# keyboard_main.net
KiCad netlist of a schematic drawn in Altium Designer
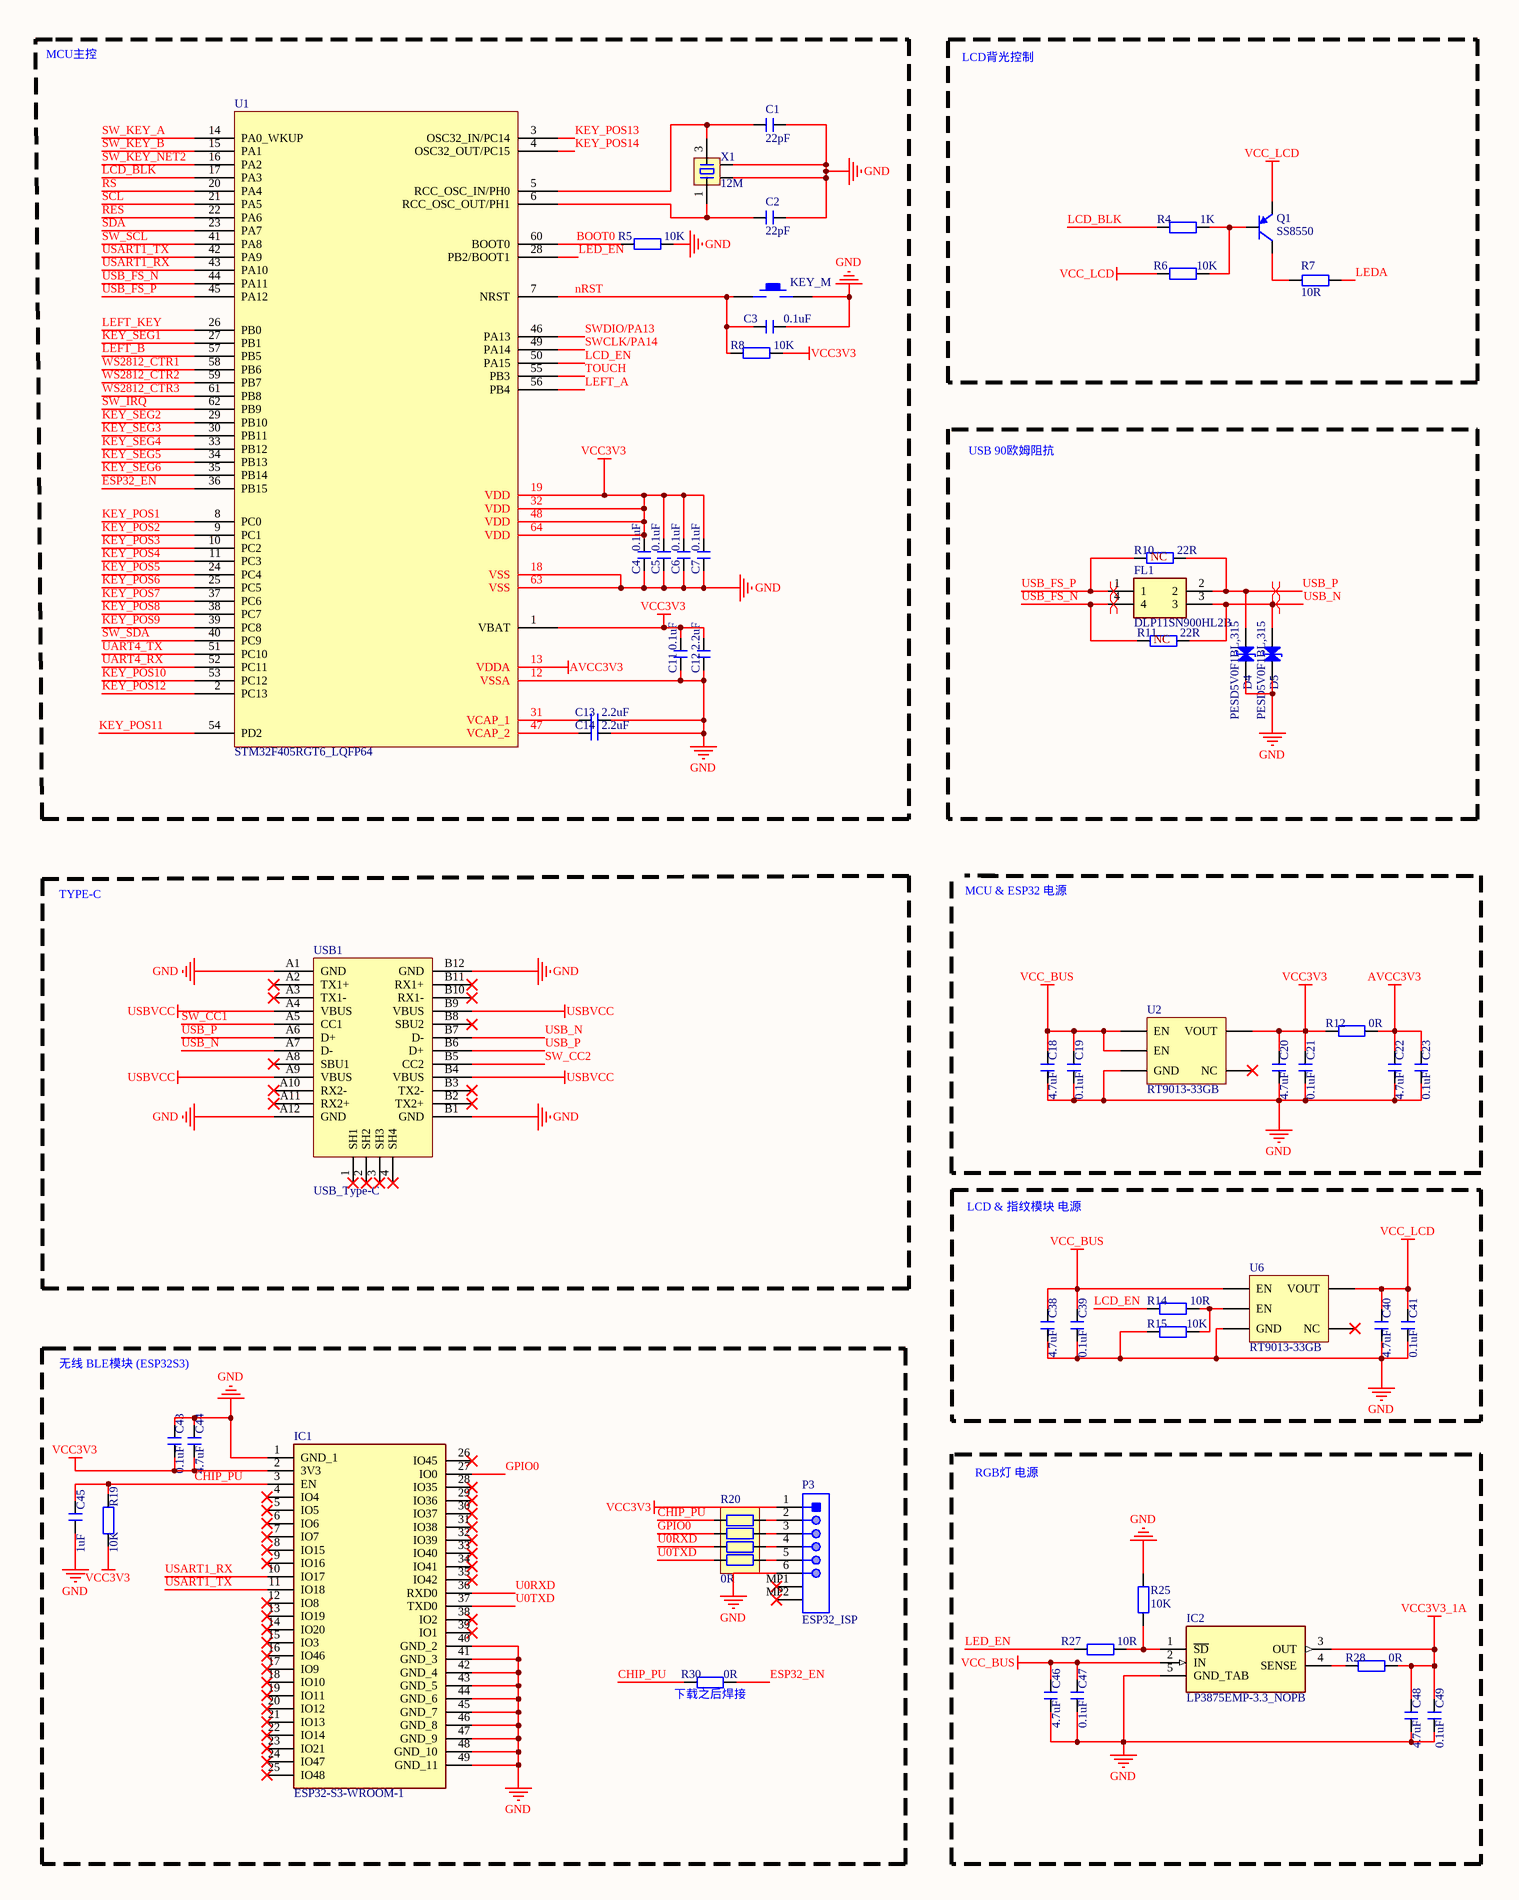
[diagram p0: keyboard_main.SchDoc, left]
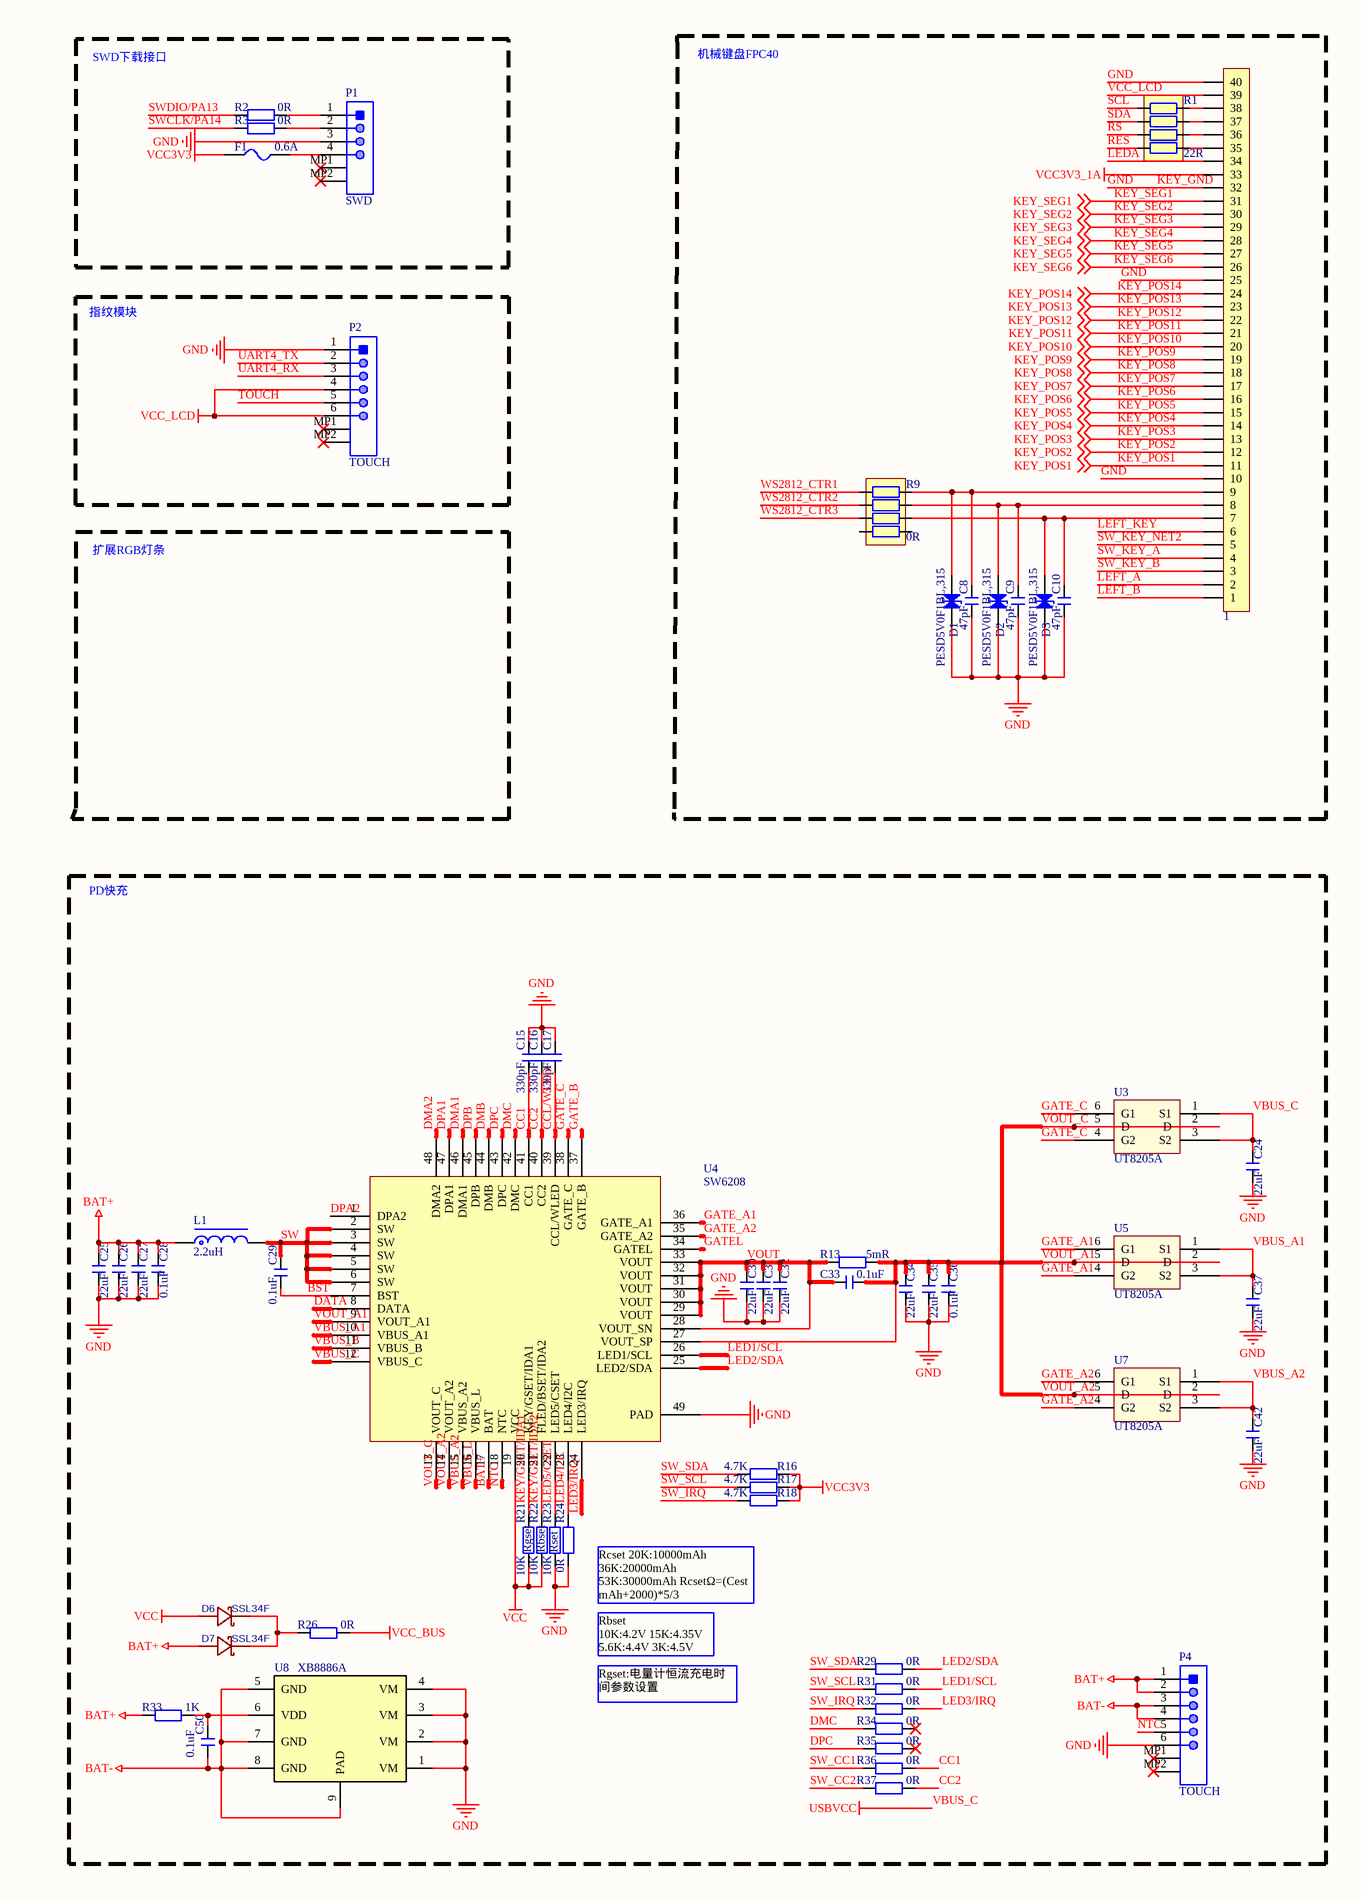
[diagram p1: keyboard_main.SchDoc, right]

(export (version "E")
  (design (tool "Eeschema 10.0.6"))
  (components
    (comp (ref "1")
      (value "FPC1.0-40P")
      (footprint "FPC0.5 2H-WS-40P")
      (description "FPC连接器")
      (fields (field (name "版权归属") "黎明电子style"))
      (libsource (lib "FPC连接器") (part "FPC-40P"))
    )
    (comp (ref "C1")
      (value "22pF")
      (footprint "C 0402_L")
      (description "贴片电容")
      (libsource (lib "0.1 - 电阻-电容-电感") (part "C"))
    )
    (comp (ref "C2")
      (value "22pF")
      (footprint "C 0402_L")
      (description "贴片电容")
      (libsource (lib "0.1 - 电阻-电容-电感") (part "C"))
    )
    (comp (ref "C3")
      (value "0.1uF")
      (footprint "C 0402_L")
      (description "贴片电容")
      (libsource (lib "0.1 - 电阻-电容-电感") (part "C"))
    )
    (comp (ref "C4")
      (value "0.1uF")
      (footprint "C 0402_L")
      (description "贴片电容")
      (libsource (lib "0.1 - 电阻-电容-电感") (part "C"))
    )
    (comp (ref "C5")
      (value "0.1uF")
      (footprint "C 0402_L")
      (description "贴片电容")
      (libsource (lib "0.1 - 电阻-电容-电感") (part "C"))
    )
    (comp (ref "C6")
      (value "0.1uF")
      (footprint "C 0402_L")
      (description "贴片电容")
      (libsource (lib "0.1 - 电阻-电容-电感") (part "C"))
    )
    (comp (ref "C7")
      (value "0.1uF")
      (footprint "C 0402_L")
      (description "贴片电容")
      (libsource (lib "0.1 - 电阻-电容-电感") (part "C"))
    )
    (comp (ref "C8")
      (value "47pF")
      (footprint "C 0402_L")
      (description "贴片电容")
      (libsource (lib "0.1 - 电阻-电容-电感") (part "C"))
    )
    (comp (ref "C9")
      (value "47pF")
      (footprint "C 0402_L")
      (description "贴片电容")
      (libsource (lib "0.1 - 电阻-电容-电感") (part "C"))
    )
    (comp (ref "C10")
      (value "47pF")
      (footprint "C 0402_L")
      (description "贴片电容")
      (libsource (lib "0.1 - 电阻-电容-电感") (part "C"))
    )
    (comp (ref "C11")
      (value "0.1uF")
      (footprint "C 0402_L")
      (description "贴片电容")
      (libsource (lib "0.1 - 电阻-电容-电感") (part "C"))
    )
    (comp (ref "C12")
      (value "2.2uF")
      (footprint "C 0402_L")
      (description "贴片电容")
      (libsource (lib "0.1 - 电阻-电容-电感") (part "C"))
    )
    (comp (ref "C13")
      (value "2.2uF")
      (footprint "C 0402_L")
      (description "贴片电容")
      (libsource (lib "0.1 - 电阻-电容-电感") (part "C"))
    )
    (comp (ref "C14")
      (value "2.2uF")
      (footprint "C 0402_L")
      (description "贴片电容")
      (libsource (lib "0.1 - 电阻-电容-电感") (part "C"))
    )
    (comp (ref "C15")
      (value "330pF")
      (footprint "C 0402_L")
      (description "贴片电容")
      (libsource (lib "0.1 - 电阻-电容-电感") (part "C"))
    )
    (comp (ref "C16")
      (value "330pF")
      (footprint "C 0402_L")
      (description "贴片电容")
      (libsource (lib "0.1 - 电阻-电容-电感") (part "C"))
    )
    (comp (ref "C17")
      (value "330pF")
      (footprint "C 0402_L")
      (description "贴片电容")
      (libsource (lib "0.1 - 电阻-电容-电感") (part "C"))
    )
    (comp (ref "C18")
      (value "4.7uF")
      (footprint "C 0402_L")
      (description "贴片电容")
      (libsource (lib "0.1 - 电阻-电容-电感") (part "C"))
    )
    (comp (ref "C19")
      (value "0.1uF")
      (footprint "C 0402_L")
      (description "贴片电容")
      (libsource (lib "0.1 - 电阻-电容-电感") (part "C"))
    )
    (comp (ref "C20")
      (value "4.7uF")
      (footprint "C 0402_L")
      (description "贴片电容")
      (libsource (lib "0.1 - 电阻-电容-电感") (part "C"))
    )
    (comp (ref "C21")
      (value "0.1uF")
      (footprint "C 0402_L")
      (description "贴片电容")
      (libsource (lib "0.1 - 电阻-电容-电感") (part "C"))
    )
    (comp (ref "C22")
      (value "4.7uF")
      (footprint "C 0402_L")
      (description "贴片电容")
      (libsource (lib "0.1 - 电阻-电容-电感") (part "C"))
    )
    (comp (ref "C23")
      (value "0.1uF")
      (footprint "C 0402_L")
      (description "贴片电容")
      (libsource (lib "0.1 - 电阻-电容-电感") (part "C"))
    )
    (comp (ref "C24")
      (value "22uF")
      (footprint "C 0805_L")
      (description "贴片电容")
      (libsource (lib "0.1 - 电阻-电容-电感") (part "C"))
    )
    (comp (ref "C25")
      (value "22uF")
      (footprint "C 0805_L")
      (description "贴片电容")
      (libsource (lib "0.1 - 电阻-电容-电感") (part "C"))
    )
    (comp (ref "C26")
      (value "22uF")
      (footprint "C 0805_L")
      (description "贴片电容")
      (libsource (lib "0.1 - 电阻-电容-电感") (part "C"))
    )
    (comp (ref "C27")
      (value "22uF")
      (footprint "C 0805_L")
      (description "贴片电容")
      (libsource (lib "0.1 - 电阻-电容-电感") (part "C"))
    )
    (comp (ref "C28")
      (value "0.1uF")
      (footprint "C 0805_L")
      (description "贴片电容")
      (libsource (lib "0.1 - 电阻-电容-电感") (part "C"))
    )
    (comp (ref "C29")
      (value "0.1uF")
      (footprint "C 0603_L")
      (description "贴片电容")
      (libsource (lib "0.1 - 电阻-电容-电感") (part "C"))
    )
    (comp (ref "C30")
      (value "22uF")
      (footprint "C 0805_L")
      (description "贴片电容")
      (libsource (lib "0.1 - 电阻-电容-电感") (part "C"))
    )
    (comp (ref "C31")
      (value "22uF")
      (footprint "C 0805_L")
      (description "贴片电容")
      (libsource (lib "0.1 - 电阻-电容-电感") (part "C"))
    )
    (comp (ref "C32")
      (value "22uF")
      (footprint "C 0805_L")
      (description "贴片电容")
      (libsource (lib "0.1 - 电阻-电容-电感") (part "C"))
    )
    (comp (ref "C33")
      (value "0.1uF")
      (footprint "C 0805_L")
      (description "贴片电容")
      (libsource (lib "0.1 - 电阻-电容-电感") (part "C"))
    )
    (comp (ref "C34")
      (value "22uF")
      (footprint "C 0805_L")
      (description "贴片电容")
      (libsource (lib "0.1 - 电阻-电容-电感") (part "C"))
    )
    (comp (ref "C35")
      (value "22uF")
      (footprint "C 0805_L")
      (description "贴片电容")
      (libsource (lib "0.1 - 电阻-电容-电感") (part "C"))
    )
    (comp (ref "C36")
      (value "0.1uF")
      (footprint "C 0805_L")
      (description "贴片电容")
      (libsource (lib "0.1 - 电阻-电容-电感") (part "C"))
    )
    (comp (ref "C37")
      (value "22uF")
      (footprint "C 0805_L")
      (description "贴片电容")
      (libsource (lib "0.1 - 电阻-电容-电感") (part "C"))
    )
    (comp (ref "C38")
      (value "4.7uF")
      (footprint "C 0402_L")
      (description "贴片电容")
      (libsource (lib "0.1 - 电阻-电容-电感") (part "C"))
    )
    (comp (ref "C39")
      (value "0.1uF")
      (footprint "C 0402_L")
      (description "贴片电容")
      (libsource (lib "0.1 - 电阻-电容-电感") (part "C"))
    )
    (comp (ref "C40")
      (value "4.7uF")
      (footprint "C 0402_L")
      (description "贴片电容")
      (libsource (lib "0.1 - 电阻-电容-电感") (part "C"))
    )
    (comp (ref "C41")
      (value "0.1uF")
      (footprint "C 0402_L")
      (description "贴片电容")
      (libsource (lib "0.1 - 电阻-电容-电感") (part "C"))
    )
    (comp (ref "C42")
      (value "22uF")
      (footprint "C 0805_L")
      (description "贴片电容")
      (libsource (lib "0.1 - 电阻-电容-电感") (part "C"))
    )
    (comp (ref "C43")
      (value "0.1uF")
      (footprint "C 0402_L")
      (description "贴片电容")
      (libsource (lib "0.1 - 电阻-电容-电感") (part "C"))
    )
    (comp (ref "C44")
      (value "4.7uF")
      (footprint "C 0402_L")
      (description "贴片电容")
      (libsource (lib "0.1 - 电阻-电容-电感") (part "C"))
    )
    (comp (ref "C45")
      (value "1uF")
      (footprint "C 0402_L")
      (description "贴片电容")
      (libsource (lib "0.1 - 电阻-电容-电感") (part "C"))
    )
    (comp (ref "C46")
      (value "4.7uF")
      (footprint "C 0402_L")
      (description "贴片电容")
      (libsource (lib "0.1 - 电阻-电容-电感") (part "C"))
    )
    (comp (ref "C47")
      (value "0.1uF")
      (footprint "C 0402_L")
      (description "贴片电容")
      (libsource (lib "0.1 - 电阻-电容-电感") (part "C"))
    )
    (comp (ref "C48")
      (value "4.7uF")
      (footprint "C 0402_L")
      (description "贴片电容")
      (libsource (lib "0.1 - 电阻-电容-电感") (part "C"))
    )
    (comp (ref "C49")
      (value "0.1uF")
      (footprint "C 0402_L")
      (description "贴片电容")
      (libsource (lib "0.1 - 电阻-电容-电感") (part "C"))
    )
    (comp (ref "C50")
      (value "0.1uF")
      (footprint "C 0805_L")
      (description "贴片电容")
      (libsource (lib "0.1 - 电阻-电容-电感") (part "C"))
    )
    (comp (ref "D1")
      (value "PESD5V0F1BL,315")
      (footprint "SOD-882_L1.0-W0.6-BI")
      (description "PESD5V0F1BL,315、ESD二极管、5.5V")
      (libsource (lib "0.2 -  二极管-整流桥") (part "PESD5V0F1BL,315"))
    )
    (comp (ref "D2")
      (value "PESD5V0F1BL,315")
      (footprint "SOD-882_L1.0-W0.6-BI")
      (description "PESD5V0F1BL,315、ESD二极管、5.5V")
      (libsource (lib "0.2 -  二极管-整流桥") (part "PESD5V0F1BL,315"))
    )
    (comp (ref "D3")
      (value "PESD5V0F1BL,315")
      (footprint "SOD-882_L1.0-W0.6-BI")
      (description "PESD5V0F1BL,315、ESD二极管、5.5V")
      (libsource (lib "0.2 -  二极管-整流桥") (part "PESD5V0F1BL,315"))
    )
    (comp (ref "D4")
      (value "PESD5V0F1BL,315")
      (footprint "SOD-882_L1.0-W0.6-BI")
      (description "PESD5V0F1BL,315、ESD二极管、5.5V")
      (libsource (lib "0.2 -  二极管-整流桥") (part "PESD5V0F1BL,315"))
    )
    (comp (ref "D5")
      (value "PESD5V0F1BL,315")
      (footprint "SOD-882_L1.0-W0.6-BI")
      (description "PESD5V0F1BL,315、ESD二极管、5.5V")
      (libsource (lib "0.2 -  二极管-整流桥") (part "PESD5V0F1BL,315"))
    )
    (comp (ref "D6")
      (value "SSL34F")
      (footprint "SMAF_L3.5-W2.6-LS4.7-RD")
      (fields (field (name "BOM_SUPPLIER PART") "C1884559") (field (name "CONTRIBUTOR") "LCSC"))
      (libsource (lib "mx_pcb_library") (part "SSL34F_C1884559"))
    )
    (comp (ref "D7")
      (value "SSL34F")
      (footprint "SMAF_L3.5-W2.6-LS4.7-RD")
      (fields (field (name "BOM_SUPPLIER PART") "C1884559") (field (name "CONTRIBUTOR") "LCSC"))
      (libsource (lib "mx_pcb_library") (part "SSL34F_C1884559"))
    )
    (comp (ref "F1")
      (value "0.6A")
      (footprint "FU 0402")
      (description "贴片保险丝")
      (libsource (lib "2.0 - 保险丝-晶振-光耦") (part "FU"))
    )
    (comp (ref "FL1")
      (value "DLP11SN900HL2B")
      (footprint "vSeasky:DLP11SA350HL2B")
      (description "Filter")
      (fields (field (name "MOUSER PART NUMBER") "81-DLP11SN900HL2B"))
      (libsource (lib "vSeasky") (part "DLP11SN900HL2B"))
    )
    (comp (ref "IC1")
      (value "ESP32-S3-WROOM-1")
      (footprint "mx_pcb_library:ESP32S3WROOM1")
      (description "Integrated Circuit")
      (libsource (lib "mx_pcb_library") (part "ESP32-S3-WROOM-1"))
    )
    (comp (ref "IC2")
      (value "LP3875EMP-3.3_NOPB")
      (footprint "mx_pcb_library:SOT150P700X180-5N")
      (description "Integrated Circuit")
      (fields
        (field (name "MANUFACTURER_PART_NUMBER") "LP3875EMP-3.3/NOPB")
        (field (name "MOUSER PART NUMBER") "926-LP3875EMP33NOPB")
      )
      (libsource (lib "mx_pcb_library") (part "LP3875EMP-3.3_NOPB"))
    )
    (comp (ref "L1")
      (value "2.2uH")
      (footprint "CD32")
      (description "CD系列贴片线绕功率电感")
      (libsource (lib "0.1 - 电阻-电容-电感") (part "L-SMD"))
    )
    (comp (ref "P1")
      (value "SWD")
      (footprint "JST-SM04B-SRSS-TB_V")
      (description "Male Header, Pitch 1 mm, 1 x 4 Position, Height 2.9 mm, -25 to 85 degC, RoHS, Tape and Reel")
      (fields (field (name "MANUFACTURER") "JST"))
      (libsource (lib "JST SH Connector") (part "SM04B-SRSS-TB(LF)(SN)"))
    )
    (comp (ref "P2")
      (value "TOUCH")
      (footprint "JST-SM06B-SRSS-TB_V")
      (description "Male Header, Pitch 1 mm, 1 x 6 Position, Height 2.9 mm, -25 to 85 degC, RoHS, Tape and Reel")
      (fields (field (name "MANUFACTURER") "JST"))
      (libsource (lib "JST SH Connector") (part "SM06B-SRSS-TB(LF)(SN)"))
    )
    (comp (ref "P3")
      (value "ESP32_ISP")
      (footprint "JST-SM06B-SRSS-TB_V")
      (description "Male Header, Pitch 1 mm, 1 x 6 Position, Height 2.9 mm, -25 to 85 degC, RoHS, Tape and Reel")
      (fields (field (name "MANUFACTURER") "JST"))
      (libsource (lib "JST SH Connector") (part "SM06B-SRSS-TB(LF)(SN)"))
    )
    (comp (ref "P4")
      (value "TOUCH")
      (footprint "JST-SM06B-SRSS-TB_V")
      (description "Male Header, Pitch 1 mm, 1 x 6 Position, Height 2.9 mm, -25 to 85 degC, RoHS, Tape and Reel")
      (fields (field (name "MANUFACTURER") "JST"))
      (libsource (lib "JST SH Connector") (part "SM06B-SRSS-TB(LF)(SN)"))
    )
    (comp (ref "Q1")
      (value "SS8550")
      (footprint "SOT23-3N")
      (description "高频放大-PNP型")
      (libsource (lib "0.4 - 三极管") (part "8550-SMD"))
    )
    (comp (ref "R1")
      (value "22R")
      (footprint "RCA-8P4R-0402")
      (description "贴片排阻")
      (libsource (lib "") (part "R-8P4R_1"))
    )
    (comp (ref "R2")
      (value "0R")
      (footprint "R 0402_L")
      (description "贴片电阻")
      (libsource (lib "0.1 - 电阻-电容-电感") (part "R"))
    )
    (comp (ref "R3")
      (value "0R")
      (footprint "R 0402_L")
      (description "贴片电阻")
      (libsource (lib "0.1 - 电阻-电容-电感") (part "R"))
    )
    (comp (ref "R4")
      (value "1K")
      (footprint "R 0402_L")
      (description "贴片电阻")
      (libsource (lib "0.1 - 电阻-电容-电感") (part "R"))
    )
    (comp (ref "R5")
      (value "10K")
      (footprint "R 0402_L")
      (description "贴片电阻")
      (libsource (lib "0.1 - 电阻-电容-电感") (part "R"))
    )
    (comp (ref "R6")
      (value "10K")
      (footprint "R 0402_L")
      (description "贴片电阻")
      (libsource (lib "0.1 - 电阻-电容-电感") (part "R"))
    )
    (comp (ref "R7")
      (value "10R")
      (footprint "R 0402_L")
      (description "贴片电阻")
      (libsource (lib "0.1 - 电阻-电容-电感") (part "R"))
    )
    (comp (ref "R8")
      (value "10K")
      (footprint "R 0402_L")
      (description "贴片电阻")
      (libsource (lib "0.1 - 电阻-电容-电感") (part "R"))
    )
    (comp (ref "R9")
      (value "0R")
      (footprint "RCA-8P4R-0402")
      (description "贴片排阻")
      (libsource (lib "") (part "R-8P4R_1"))
    )
    (comp (ref "R10")
      (value "22R")
      (footprint "R 0402_L")
      (description "贴片电阻")
      (libsource (lib "0.1 - 电阻-电容-电感") (part "R"))
    )
    (comp (ref "R11")
      (value "22R")
      (footprint "R 0402_L")
      (description "贴片电阻")
      (libsource (lib "0.1 - 电阻-电容-电感") (part "R"))
    )
    (comp (ref "R12")
      (value "0R")
      (footprint "R 0402_L")
      (description "贴片电阻")
      (libsource (lib "0.1 - 电阻-电容-电感") (part "R"))
    )
    (comp (ref "R13")
      (value "5mR")
      (footprint "R 1206_L")
      (description "贴片电阻")
      (libsource (lib "0.1 - 电阻-电容-电感") (part "R"))
    )
    (comp (ref "R14")
      (value "10R")
      (footprint "R 0402_L")
      (description "贴片电阻")
      (libsource (lib "0.1 - 电阻-电容-电感") (part "R"))
    )
    (comp (ref "R15")
      (value "10K")
      (footprint "R 0402_L")
      (description "贴片电阻")
      (libsource (lib "0.1 - 电阻-电容-电感") (part "R"))
    )
    (comp (ref "R16")
      (value "4.7K")
      (footprint "R 0402_L")
      (description "贴片电阻")
      (libsource (lib "0.1 - 电阻-电容-电感") (part "R"))
    )
    (comp (ref "R17")
      (value "4.7K")
      (footprint "R 0402_L")
      (description "贴片电阻")
      (libsource (lib "0.1 - 电阻-电容-电感") (part "R"))
    )
    (comp (ref "R18")
      (value "4.7K")
      (footprint "R 0402_L")
      (description "贴片电阻")
      (libsource (lib "0.1 - 电阻-电容-电感") (part "R"))
    )
    (comp (ref "R19")
      (value "10K")
      (footprint "R 0402_L")
      (description "贴片电阻")
      (libsource (lib "0.1 - 电阻-电容-电感") (part "R"))
    )
    (comp (ref "R20")
      (value "0R")
      (footprint "RCA-8P4R-0402")
      (description "贴片排阻")
      (libsource (lib "0.1 - 电阻-电容-电感") (part "R-8P4R"))
    )
    (comp (ref "R21")
      (value "10K")
      (footprint "R 0402_L")
      (description "贴片电阻")
      (libsource (lib "0.1 - 电阻-电容-电感") (part "R"))
    )
    (comp (ref "R22")
      (value "10K")
      (footprint "R 0402_L")
      (description "贴片电阻")
      (libsource (lib "0.1 - 电阻-电容-电感") (part "R"))
    )
    (comp (ref "R23")
      (value "10K")
      (footprint "R 0402_L")
      (description "贴片电阻")
      (libsource (lib "0.1 - 电阻-电容-电感") (part "R"))
    )
    (comp (ref "R24")
      (value "0R")
      (footprint "R 0402_L")
      (description "贴片电阻")
      (libsource (lib "0.1 - 电阻-电容-电感") (part "R"))
    )
    (comp (ref "R25")
      (value "10K")
      (footprint "R 0402_L")
      (description "贴片电阻")
      (libsource (lib "0.1 - 电阻-电容-电感") (part "R"))
    )
    (comp (ref "R26")
      (value "0R")
      (footprint "R 0402_L")
      (description "贴片电阻")
      (libsource (lib "0.1 - 电阻-电容-电感") (part "R"))
    )
    (comp (ref "R27")
      (value "10R")
      (footprint "R 0402_L")
      (description "贴片电阻")
      (libsource (lib "0.1 - 电阻-电容-电感") (part "R"))
    )
    (comp (ref "R28")
      (value "0R")
      (footprint "R 0402_L")
      (description "贴片电阻")
      (libsource (lib "0.1 - 电阻-电容-电感") (part "R"))
    )
    (comp (ref "R29")
      (value "0R")
      (footprint "R 0402_L")
      (description "贴片电阻")
      (libsource (lib "0.1 - 电阻-电容-电感") (part "R"))
    )
    (comp (ref "R30")
      (value "0R")
      (footprint "R 0402_L")
      (description "贴片电阻")
      (libsource (lib "0.1 - 电阻-电容-电感") (part "R"))
    )
    (comp (ref "R31")
      (value "0R")
      (footprint "R 0402_L")
      (description "贴片电阻")
      (libsource (lib "0.1 - 电阻-电容-电感") (part "R"))
    )
    (comp (ref "R32")
      (value "0R")
      (footprint "R 0402_L")
      (description "贴片电阻")
      (libsource (lib "0.1 - 电阻-电容-电感") (part "R"))
    )
    (comp (ref "R33")
      (value "1K")
      (footprint "R 0402_L")
      (description "贴片电阻")
      (libsource (lib "0.1 - 电阻-电容-电感") (part "R"))
    )
    (comp (ref "R34")
      (value "0R")
      (footprint "R 0402_L")
      (description "贴片电阻")
      (libsource (lib "0.1 - 电阻-电容-电感") (part "R"))
    )
    (comp (ref "R35")
      (value "0R")
      (footprint "R 0402_L")
      (description "贴片电阻")
      (libsource (lib "0.1 - 电阻-电容-电感") (part "R"))
    )
    (comp (ref "R36")
      (value "0R")
      (footprint "R 0402_L")
      (description "贴片电阻")
      (libsource (lib "0.1 - 电阻-电容-电感") (part "R"))
    )
    (comp (ref "R37")
      (value "0R")
      (footprint "R 0402_L")
      (description "贴片电阻")
      (libsource (lib "0.1 - 电阻-电容-电感") (part "R"))
    )
    (comp (ref "RST1")
      (value "KEY_M")
      (footprint "SMD-3.2*4.2")
      (libsource (lib "mx_pcb_library") (part "KEY_M"))
    )
    (comp (ref "U1")
      (value "STM32F405RGT6_LQFP64")
      (footprint "LQFP-64_10X10X05P")
      (libsource (lib "mx_pcb_library") (part "STM32F405RGT6_LQFP64"))
    )
    (comp (ref "U2")
      (value "RT9013-33GB")
      (footprint "SOT23-5M")
      (libsource (lib "mx_pcb_library") (part "RT9013-33GB"))
    )
    (comp (ref "U3")
      (value "UT8205A")
      (footprint "mx_pcb_library:SOT23-6")
      (libsource (lib "mx_pcb_library") (part "UT8205A"))
    )
    (comp (ref "U4")
      (value "SW6208")
      (footprint "QFN-48_6x6")
      (description "充电宝芯片")
      (libsource (lib "mx_pcb_library") (part "SW6208"))
    )
    (comp (ref "U5")
      (value "UT8205A")
      (footprint "mx_pcb_library:SOT23-6")
      (libsource (lib "mx_pcb_library") (part "UT8205A"))
    )
    (comp (ref "U6")
      (value "RT9013-33GB")
      (footprint "SOT23-5M")
      (libsource (lib "mx_pcb_library") (part "RT9013-33GB"))
    )
    (comp (ref "U7")
      (value "UT8205A")
      (footprint "mx_pcb_library:SOT23-6")
      (libsource (lib "mx_pcb_library") (part "UT8205A"))
    )
    (comp (ref "U8")
      (value "XB8886A")
      (footprint "mx_pcb_library:SO-8-PAD")
      (fields (field (name "MF") "Texas Instruments") (field (name "MP") "NE5532D"))
      (libsource (lib "mx_pcb_library") (part "XB8886A"))
    )
    (comp (ref "USB1")
      (value "USB_Type-C")
      (footprint "Type-C-TOP")
      (libsource (lib "mx_pcb_library") (part "USB_Type-C"))
    )
    (comp (ref "X1")
      (value "12M")
      (footprint "OSC 3225-4P")
      (description "4脚无源晶振")
      (libsource (lib "2.0 - 保险丝-晶振-光耦") (part "XTAL-4P"))
    )
  )
  (nets
    (net (code "1") (name "/BOOT0") (class "Default")
      (node (ref "R5") (pin "1") (pinfunction "1_1") (pintype "passive"))
      (node (ref "U1") (pin "60") (pinfunction "BOOT0_60") (pintype "passive"))
    )
    (net (code "2") (name "/BST") (class "Default")
      (node (ref "C29") (pin "1") (pinfunction "1_1") (pintype "passive"))
      (node (ref "U4") (pin "7") (pinfunction "BST_7") (pintype "passive"))
    )
    (net (code "3") (name "/CC1") (class "Default")
      (node (ref "C15") (pin "1") (pinfunction "1_1") (pintype "passive"))
      (node (ref "R36") (pin "2") (pinfunction "2_2") (pintype "passive"))
      (node (ref "U4") (pin "41") (pinfunction "CC1_41") (pintype "passive"))
    )
    (net (code "4") (name "/CC2") (class "Default")
      (node (ref "C16") (pin "1") (pinfunction "1_1") (pintype "passive"))
      (node (ref "R37") (pin "2") (pinfunction "2_2") (pintype "passive"))
      (node (ref "U4") (pin "40") (pinfunction "CC2_40") (pintype "passive"))
    )
    (net (code "5") (name "/CCL{slash}WLED") (class "Default")
      (node (ref "C17") (pin "1") (pinfunction "1_1") (pintype "passive"))
      (node (ref "U4") (pin "39") (pinfunction "CCL/WLED_39") (pintype "passive"))
    )
    (net (code "6") (name "/CHIP_PU") (class "Default")
      (node (ref "C45") (pin "1") (pinfunction "1_1") (pintype "passive"))
      (node (ref "IC1") (pin "3") (pinfunction "EN_3") (pintype "passive"))
      (node (ref "R19") (pin "1") (pinfunction "1_1") (pintype "passive"))
      (node (ref "R20") (pin "8") (pinfunction "8_8") (pintype "passive"))
      (node (ref "R30") (pin "1") (pinfunction "1_1") (pintype "passive"))
    )
    (net (code "7") (name "/DATA") (class "Default")
      (node (ref "U4") (pin "8") (pinfunction "DATA_8") (pintype "passive"))
    )
    (net (code "8") (name "/DMA1") (class "Default")
      (node (ref "U4") (pin "46") (pinfunction "DMA1_46") (pintype "passive"))
    )
    (net (code "9") (name "/DMA2") (class "Default")
      (node (ref "U4") (pin "48") (pinfunction "DMA2_48") (pintype "passive"))
    )
    (net (code "10") (name "/DMB") (class "Default")
      (node (ref "U4") (pin "44") (pinfunction "DMB_44") (pintype "passive"))
    )
    (net (code "11") (name "/DMC") (class "Default")
      (node (ref "R34") (pin "1") (pinfunction "1_1") (pintype "passive"))
      (node (ref "U4") (pin "42") (pinfunction "DMC_42") (pintype "passive"))
    )
    (net (code "12") (name "/DPA1") (class "Default")
      (node (ref "U4") (pin "47") (pinfunction "DPA1_47") (pintype "passive"))
    )
    (net (code "13") (name "/DPA2") (class "Default")
      (node (ref "U4") (pin "1") (pinfunction "DPA2_1") (pintype "passive"))
    )
    (net (code "14") (name "/DPB") (class "Default")
      (node (ref "U4") (pin "45") (pinfunction "DPB_45") (pintype "passive"))
    )
    (net (code "15") (name "/DPC") (class "Default")
      (node (ref "R35") (pin "1") (pinfunction "1_1") (pintype "passive"))
      (node (ref "U4") (pin "43") (pinfunction "DPC_43") (pintype "passive"))
    )
    (net (code "16") (name "/ESP32_EN") (class "Default")
      (node (ref "R30") (pin "2") (pinfunction "2_2") (pintype "passive"))
      (node (ref "U1") (pin "36") (pinfunction "PB15_36") (pintype "passive"))
    )
    (net (code "17") (name "/GATEL") (class "Default")
      (node (ref "U4") (pin "34") (pinfunction "GATEL_34") (pintype "passive"))
    )
    (net (code "18") (name "/GATE_A1") (class "Default")
      (node (ref "U4") (pin "36") (pinfunction "GATE_A1_36") (pintype "passive"))
      (node (ref "U5") (pin "4") (pinfunction "G2_4") (pintype "passive"))
      (node (ref "U5") (pin "6") (pinfunction "G1_6") (pintype "passive"))
    )
    (net (code "19") (name "/GATE_A2") (class "Default")
      (node (ref "U4") (pin "35") (pinfunction "GATE_A2_35") (pintype "passive"))
      (node (ref "U7") (pin "4") (pinfunction "G2_4") (pintype "passive"))
      (node (ref "U7") (pin "6") (pinfunction "G1_6") (pintype "passive"))
    )
    (net (code "20") (name "/GATE_B") (class "Default")
      (node (ref "U4") (pin "37") (pinfunction "GATE_B_37") (pintype "passive"))
    )
    (net (code "21") (name "/GATE_C") (class "Default")
      (node (ref "U3") (pin "4") (pinfunction "G2_4") (pintype "passive"))
      (node (ref "U3") (pin "6") (pinfunction "G1_6") (pintype "passive"))
      (node (ref "U4") (pin "38") (pinfunction "GATE_C_38") (pintype "passive"))
    )
    (net (code "22") (name "/GPIO0") (class "Default")
      (node (ref "IC1") (pin "27") (pinfunction "IO0_27") (pintype "passive"))
      (node (ref "R20") (pin "7") (pinfunction "7_7") (pintype "passive"))
    )
    (net (code "23") (name "/KEY{slash}GSET{slash}IDA1") (class "Default")
      (node (ref "R21") (pin "1") (pinfunction "1_1") (pintype "passive"))
      (node (ref "U4") (pin "20") (pinfunction "KEY/GSET/IDA1_20") (pintype "passive"))
    )
    (net (code "24") (name "/KEY{slash}GSET{slash}IDA2") (class "Default")
      (node (ref "R22") (pin "1") (pinfunction "1_1") (pintype "passive"))
      (node (ref "U4") (pin "21") (pinfunction "FLED/BSET/IDA2_21") (pintype "passive"))
    )
    (net (code "25") (name "/LCD_BLK") (class "Default")
      (node (ref "R4") (pin "1") (pinfunction "1_1") (pintype "passive"))
      (node (ref "U1") (pin "17") (pinfunction "PA3_17") (pintype "passive"))
    )
    (net (code "26") (name "/LCD_EN") (class "Default")
      (node (ref "R14") (pin "1") (pinfunction "1_1") (pintype "passive"))
      (node (ref "U1") (pin "50") (pinfunction "PA15_50") (pintype "passive"))
    )
    (net (code "27") (name "/LED1{slash}SCL") (class "Default")
      (node (ref "R31") (pin "2") (pinfunction "2_2") (pintype "passive"))
      (node (ref "U4") (pin "26") (pinfunction "LED1/SCL_26") (pintype "passive"))
    )
    (net (code "28") (name "/LED2{slash}SDA") (class "Default")
      (node (ref "R29") (pin "2") (pinfunction "2_2") (pintype "passive"))
      (node (ref "U4") (pin "25") (pinfunction "LED2/SDA_25") (pintype "passive"))
    )
    (net (code "29") (name "/LED3{slash}IRQ") (class "Default")
      (node (ref "R32") (pin "2") (pinfunction "2_2") (pintype "passive"))
      (node (ref "U4") (pin "24") (pinfunction "LED3/IRQ_24") (pintype "passive"))
    )
    (net (code "30") (name "/LED4{slash}I2C") (class "Default")
      (node (ref "R24") (pin "1") (pinfunction "1_1") (pintype "passive"))
      (node (ref "U4") (pin "23") (pinfunction "LED4/I2C_23") (pintype "passive"))
    )
    (net (code "31") (name "/LED5{slash}CSET") (class "Default")
      (node (ref "R23") (pin "1") (pinfunction "1_1") (pintype "passive"))
      (node (ref "U4") (pin "22") (pinfunction "LED5/CSET_22") (pintype "passive"))
    )
    (net (code "32") (name "/LEDA") (class "Default")
      (node (ref "1") (pin "34") (pinfunction "34_34") (pintype "passive"))
      (node (ref "R7") (pin "1") (pinfunction "1_1") (pintype "passive"))
    )
    (net (code "33") (name "/LED_EN") (class "Default")
      (node (ref "R27") (pin "1") (pinfunction "1_1") (pintype "passive"))
      (node (ref "U1") (pin "28") (pinfunction "PB2/BOOT1_28") (pintype "passive"))
    )
    (net (code "34") (name "/LEFT_A") (class "Default")
      (node (ref "1") (pin "2") (pinfunction "2_2") (pintype "passive"))
      (node (ref "U1") (pin "56") (pinfunction "PB4_56") (pintype "passive"))
    )
    (net (code "35") (name "/LEFT_B") (class "Default")
      (node (ref "1") (pin "1") (pinfunction "1_1") (pintype "passive"))
      (node (ref "U1") (pin "57") (pinfunction "PB5_57") (pintype "passive"))
    )
    (net (code "36") (name "/LEFT_KEY") (class "Default")
      (node (ref "1") (pin "6") (pinfunction "6_6") (pintype "passive"))
      (node (ref "U1") (pin "26") (pinfunction "PB0_26") (pintype "passive"))
    )
    (net (code "37") (name "/NTC") (class "Default")
      (node (ref "P4") (pin "5") (pinfunction "5_5") (pintype "passive"))
      (node (ref "U4") (pin "18") (pinfunction "NTC_18") (pintype "passive"))
    )
    (net (code "38") (name "/RES") (class "Default")
      (node (ref "R1") (pin "4") (pinfunction "4_4") (pintype "passive"))
      (node (ref "U1") (pin "22") (pinfunction "PA6_22") (pintype "passive"))
    )
    (net (code "39") (name "/RS") (class "Default")
      (node (ref "R1") (pin "3") (pinfunction "3_3") (pintype "passive"))
      (node (ref "U1") (pin "20") (pinfunction "PA4_20") (pintype "passive"))
    )
    (net (code "40") (name "/SCL") (class "Default")
      (node (ref "R1") (pin "1") (pinfunction "1_1") (pintype "passive"))
      (node (ref "U1") (pin "21") (pinfunction "PA5_21") (pintype "passive"))
    )
    (net (code "41") (name "/SDA") (class "Default")
      (node (ref "R1") (pin "2") (pinfunction "2_2") (pintype "passive"))
      (node (ref "U1") (pin "23") (pinfunction "PA7_23") (pintype "passive"))
    )
    (net (code "42") (name "/SW") (class "Default")
      (node (ref "C29") (pin "2") (pinfunction "2_2") (pintype "passive"))
      (node (ref "L1") (pin "2") (pinfunction "2_2") (pintype "passive"))
      (node (ref "U4") (pin "2") (pinfunction "SW_2") (pintype "passive"))
      (node (ref "U4") (pin "3") (pinfunction "SW_3") (pintype "passive"))
      (node (ref "U4") (pin "4") (pinfunction "SW_4") (pintype "passive"))
      (node (ref "U4") (pin "5") (pinfunction "SW_5") (pintype "passive"))
      (node (ref "U4") (pin "6") (pinfunction "SW_6") (pintype "passive"))
    )
    (net (code "43") (name "/SWCLK{slash}PA14") (class "Default")
      (node (ref "R3") (pin "1") (pinfunction "1_1") (pintype "passive"))
      (node (ref "U1") (pin "49") (pinfunction "PA14_49") (pintype "passive"))
    )
    (net (code "44") (name "/SWDIO{slash}PA13") (class "Default")
      (node (ref "R2") (pin "1") (pinfunction "1_1") (pintype "passive"))
      (node (ref "U1") (pin "46") (pinfunction "PA13_46") (pintype "passive"))
    )
    (net (code "45") (name "/SW_CC1") (class "Default")
      (node (ref "R36") (pin "1") (pinfunction "1_1") (pintype "passive"))
      (node (ref "USB1") (pin "A5") (pinfunction "CC1_A5") (pintype "passive"))
    )
    (net (code "46") (name "/SW_CC2") (class "Default")
      (node (ref "R37") (pin "1") (pinfunction "1_1") (pintype "passive"))
      (node (ref "USB1") (pin "B5") (pinfunction "CC2_B5") (pintype "passive"))
    )
    (net (code "47") (name "/SW_IRQ") (class "Default")
      (node (ref "R18") (pin "2") (pinfunction "2_2") (pintype "passive"))
      (node (ref "R32") (pin "1") (pinfunction "1_1") (pintype "passive"))
      (node (ref "U1") (pin "62") (pinfunction "PB9_62") (pintype "passive"))
    )
    (net (code "48") (name "/SW_KEY_A") (class "Default")
      (node (ref "1") (pin "4") (pinfunction "4_4") (pintype "passive"))
      (node (ref "U1") (pin "14") (pinfunction "PA0_WKUP_14") (pintype "passive"))
    )
    (net (code "49") (name "/SW_KEY_B") (class "Default")
      (node (ref "1") (pin "3") (pinfunction "3_3") (pintype "passive"))
      (node (ref "U1") (pin "15") (pinfunction "PA1_15") (pintype "passive"))
    )
    (net (code "50") (name "/SW_KEY_NET2") (class "Default")
      (node (ref "1") (pin "5") (pinfunction "5_5") (pintype "passive"))
      (node (ref "U1") (pin "16") (pinfunction "PA2_16") (pintype "passive"))
    )
    (net (code "51") (name "/SW_SCL") (class "Default")
      (node (ref "R17") (pin "2") (pinfunction "2_2") (pintype "passive"))
      (node (ref "R31") (pin "1") (pinfunction "1_1") (pintype "passive"))
      (node (ref "U1") (pin "41") (pinfunction "PA8_41") (pintype "passive"))
    )
    (net (code "52") (name "/SW_SDA") (class "Default")
      (node (ref "R16") (pin "2") (pinfunction "2_2") (pintype "passive"))
      (node (ref "R29") (pin "1") (pinfunction "1_1") (pintype "passive"))
      (node (ref "U1") (pin "40") (pinfunction "PC9_40") (pintype "passive"))
    )
    (net (code "53") (name "/TOUCH") (class "Default")
      (node (ref "P2") (pin "5") (pinfunction "5_5") (pintype "passive"))
      (node (ref "U1") (pin "55") (pinfunction "PB3_55") (pintype "passive"))
    )
    (net (code "54") (name "/U0RXD") (class "Default")
      (node (ref "IC1") (pin "36") (pinfunction "RXD0_36") (pintype "passive"))
      (node (ref "R20") (pin "6") (pinfunction "6_6") (pintype "passive"))
    )
    (net (code "55") (name "/U0TXD") (class "Default")
      (node (ref "IC1") (pin "37") (pinfunction "TXD0_37") (pintype "passive"))
      (node (ref "R20") (pin "5") (pinfunction "5_5") (pintype "passive"))
    )
    (net (code "56") (name "/UART4_RX") (class "Default")
      (node (ref "P2") (pin "3") (pinfunction "3_3") (pintype "passive"))
      (node (ref "U1") (pin "52") (pinfunction "PC11_52") (pintype "passive"))
    )
    (net (code "57") (name "/UART4_TX") (class "Default")
      (node (ref "P2") (pin "2") (pinfunction "2_2") (pintype "passive"))
      (node (ref "U1") (pin "51") (pinfunction "PC10_51") (pintype "passive"))
    )
    (net (code "58") (name "/USART1_RX") (class "Default")
      (node (ref "IC1") (pin "10") (pinfunction "IO17_10") (pintype "passive"))
      (node (ref "U1") (pin "43") (pinfunction "PA10_43") (pintype "passive"))
    )
    (net (code "59") (name "/USART1_TX") (class "Default")
      (node (ref "IC1") (pin "11") (pinfunction "IO18_11") (pintype "passive"))
      (node (ref "U1") (pin "42") (pinfunction "PA9_42") (pintype "passive"))
    )
    (net (code "60") (name "/USB_FS_N") (class "Default")
      (node (ref "FL1") (pin "4") (pinfunction "4_4") (pintype "passive"))
      (node (ref "R11") (pin "1") (pinfunction "1_1") (pintype "passive"))
      (node (ref "U1") (pin "44") (pinfunction "PA11_44") (pintype "passive"))
    )
    (net (code "61") (name "/USB_FS_P") (class "Default")
      (node (ref "FL1") (pin "1") (pinfunction "1_1") (pintype "passive"))
      (node (ref "R10") (pin "1") (pinfunction "1_1") (pintype "passive"))
      (node (ref "U1") (pin "45") (pinfunction "PA12_45") (pintype "passive"))
    )
    (net (code "62") (name "/USB_N") (class "Default")
      (node (ref "D5") (pin "1") (pinfunction "A_1") (pintype "passive"))
      (node (ref "FL1") (pin "3") (pinfunction "3_3") (pintype "passive"))
      (node (ref "R11") (pin "2") (pinfunction "2_2") (pintype "passive"))
      (node (ref "USB1") (pin "A7") (pinfunction "D-_A7") (pintype "passive"))
      (node (ref "USB1") (pin "B7") (pinfunction "D-_B7") (pintype "passive"))
    )
    (net (code "63") (name "/USB_P") (class "Default")
      (node (ref "D4") (pin "1") (pinfunction "A_1") (pintype "passive"))
      (node (ref "FL1") (pin "2") (pinfunction "2_2") (pintype "passive"))
      (node (ref "R10") (pin "2") (pinfunction "2_2") (pintype "passive"))
      (node (ref "USB1") (pin "A6") (pinfunction "D+_A6") (pintype "passive"))
      (node (ref "USB1") (pin "B6") (pinfunction "D+_B6") (pintype "passive"))
    )
    (net (code "64") (name "/VBUS_A1") (class "Default")
      (node (ref "C37") (pin "2") (pinfunction "2_2") (pintype "passive"))
      (node (ref "U4") (pin "10") (pinfunction "VBUS_A1_10") (pintype "passive"))
      (node (ref "U5") (pin "1") (pinfunction "S1_1") (pintype "passive"))
      (node (ref "U5") (pin "3") (pinfunction "S2_3") (pintype "passive"))
    )
    (net (code "65") (name "/VBUS_A2") (class "Default")
      (node (ref "C42") (pin "2") (pinfunction "2_2") (pintype "passive"))
      (node (ref "U4") (pin "15") (pinfunction "VBUS_A2_15") (pintype "passive"))
      (node (ref "U7") (pin "1") (pinfunction "S1_1") (pintype "passive"))
      (node (ref "U7") (pin "3") (pinfunction "S2_3") (pintype "passive"))
    )
    (net (code "66") (name "/VBUS_B") (class "Default")
      (node (ref "U4") (pin "11") (pinfunction "VBUS_B_11") (pintype "passive"))
    )
    (net (code "67") (name "/VBUS_L") (class "Default")
      (node (ref "U4") (pin "16") (pinfunction "VBUS_L_16") (pintype "passive"))
    )
    (net (code "68") (name "/VOUT") (class "Default")
      (node (ref "C30") (pin "2") (pinfunction "2_2") (pintype "passive"))
      (node (ref "C31") (pin "2") (pinfunction "2_2") (pintype "passive"))
      (node (ref "C32") (pin "2") (pinfunction "2_2") (pintype "passive"))
      (node (ref "C33") (pin "1") (pinfunction "1_1") (pintype "passive"))
      (node (ref "R13") (pin "1") (pinfunction "1_1") (pintype "passive"))
      (node (ref "U4") (pin "28") (pinfunction "VOUT_SN_28") (pintype "passive"))
      (node (ref "U4") (pin "29") (pinfunction "VOUT_29") (pintype "passive"))
      (node (ref "U4") (pin "30") (pinfunction "VOUT_30") (pintype "passive"))
      (node (ref "U4") (pin "31") (pinfunction "VOUT_31") (pintype "passive"))
      (node (ref "U4") (pin "32") (pinfunction "VOUT_32") (pintype "passive"))
      (node (ref "U4") (pin "33") (pinfunction "VOUT_33") (pintype "passive"))
    )
    (net (code "69") (name "/VOUT_A1") (class "Default")
      (node (ref "C33") (pin "2") (pinfunction "2_2") (pintype "passive"))
      (node (ref "C34") (pin "2") (pinfunction "2_2") (pintype "passive"))
      (node (ref "C35") (pin "2") (pinfunction "2_2") (pintype "passive"))
      (node (ref "C36") (pin "2") (pinfunction "2_2") (pintype "passive"))
      (node (ref "R13") (pin "2") (pinfunction "2_2") (pintype "passive"))
      (node (ref "U3") (pin "2") (pinfunction "D_2") (pintype "passive"))
      (node (ref "U3") (pin "5") (pinfunction "D_5") (pintype "passive"))
      (node (ref "U4") (pin "13") (pinfunction "VOUT_C_13") (pintype "passive"))
      (node (ref "U4") (pin "14") (pinfunction "VOUT_A2_14") (pintype "passive"))
      (node (ref "U4") (pin "27") (pinfunction "VOUT_SP_27") (pintype "passive"))
      (node (ref "U4") (pin "9") (pinfunction "VOUT_A1_9") (pintype "passive"))
      (node (ref "U5") (pin "2") (pinfunction "D_2") (pintype "passive"))
      (node (ref "U5") (pin "5") (pinfunction "D_5") (pintype "passive"))
      (node (ref "U7") (pin "2") (pinfunction "D_2") (pintype "passive"))
      (node (ref "U7") (pin "5") (pinfunction "D_5") (pintype "passive"))
    )
    (net (code "70") (name "/WS2812_CTR1") (class "Default")
      (node (ref "R9") (pin "1") (pinfunction "1_1") (pintype "passive"))
      (node (ref "U1") (pin "58") (pinfunction "PB6_58") (pintype "passive"))
    )
    (net (code "71") (name "/WS2812_CTR2") (class "Default")
      (node (ref "R9") (pin "2") (pinfunction "2_2") (pintype "passive"))
      (node (ref "U1") (pin "59") (pinfunction "PB7_59") (pintype "passive"))
    )
    (net (code "72") (name "/WS2812_CTR3") (class "Default")
      (node (ref "R9") (pin "3") (pinfunction "3_3") (pintype "passive"))
      (node (ref "U1") (pin "61") (pinfunction "PB8_61") (pintype "passive"))
    )
    (net (code "73") (name "/nRST") (class "Default")
      (node (ref "C3") (pin "1") (pinfunction "1_1") (pintype "passive"))
      (node (ref "R8") (pin "1") (pinfunction "1_1") (pintype "passive"))
      (node (ref "RST1") (pin "1") (pinfunction "1_1") (pintype "passive"))
      (node (ref "U1") (pin "7") (pinfunction "NRST_7") (pintype "passive"))
    )
    (net (code "74") (name "AVCC3V3") (class "Default")
      (node (ref "C22") (pin "1") (pinfunction "1_1") (pintype "passive"))
      (node (ref "C23") (pin "1") (pinfunction "1_1") (pintype "passive"))
      (node (ref "R12") (pin "2") (pinfunction "2_2") (pintype "passive"))
      (node (ref "U1") (pin "13") (pinfunction "VDDA_13") (pintype "passive"))
    )
    (net (code "75") (name "BAT+") (class "Default")
      (node (ref "C25") (pin "2") (pinfunction "2_2") (pintype "passive"))
      (node (ref "C26") (pin "2") (pinfunction "2_2") (pintype "passive"))
      (node (ref "C27") (pin "2") (pinfunction "2_2") (pintype "passive"))
      (node (ref "C28") (pin "2") (pinfunction "2_2") (pintype "passive"))
      (node (ref "D7") (pin "2") (pinfunction "A_2") (pintype "passive"))
      (node (ref "L1") (pin "1") (pinfunction "1_1") (pintype "passive"))
      (node (ref "P4") (pin "1") (pinfunction "1_1") (pintype "passive"))
      (node (ref "P4") (pin "2") (pinfunction "2_2") (pintype "passive"))
      (node (ref "R33") (pin "1") (pinfunction "1_1") (pintype "passive"))
      (node (ref "U4") (pin "17") (pinfunction "BAT_17") (pintype "passive"))
    )
    (net (code "76") (name "BAT-") (class "Default")
      (node (ref "C50") (pin "1") (pinfunction "1_1") (pintype "passive"))
      (node (ref "P4") (pin "3") (pinfunction "3_3") (pintype "passive"))
      (node (ref "P4") (pin "4") (pinfunction "4_4") (pintype "passive"))
      (node (ref "U8") (pin "5") (pinfunction "GND_5") (pintype "passive"))
      (node (ref "U8") (pin "7") (pinfunction "GND_7") (pintype "passive"))
      (node (ref "U8") (pin "8") (pinfunction "GND_8") (pintype "passive"))
      (node (ref "U8") (pin "9") (pinfunction "PAD_9") (pintype "passive"))
    )
    (net (code "77") (name "GND") (class "Default")
      (node (ref "1") (pin "10") (pinfunction "10_10") (pintype "passive"))
      (node (ref "1") (pin "25") (pinfunction "25_25") (pintype "passive"))
      (node (ref "1") (pin "32") (pinfunction "32_32") (pintype "passive"))
      (node (ref "1") (pin "40") (pinfunction "40_40") (pintype "passive"))
      (node (ref "C1") (pin "2") (pinfunction "2_2") (pintype "passive"))
      (node (ref "C10") (pin "1") (pinfunction "1_1") (pintype "passive"))
      (node (ref "C11") (pin "1") (pinfunction "1_1") (pintype "passive"))
      (node (ref "C12") (pin "1") (pinfunction "1_1") (pintype "passive"))
      (node (ref "C13") (pin "1") (pinfunction "1_1") (pintype "passive"))
      (node (ref "C14") (pin "1") (pinfunction "1_1") (pintype "passive"))
      (node (ref "C15") (pin "2") (pinfunction "2_2") (pintype "passive"))
      (node (ref "C16") (pin "2") (pinfunction "2_2") (pintype "passive"))
      (node (ref "C17") (pin "2") (pinfunction "2_2") (pintype "passive"))
      (node (ref "C18") (pin "2") (pinfunction "2_2") (pintype "passive"))
      (node (ref "C19") (pin "2") (pinfunction "2_2") (pintype "passive"))
      (node (ref "C2") (pin "2") (pinfunction "2_2") (pintype "passive"))
      (node (ref "C20") (pin "2") (pinfunction "2_2") (pintype "passive"))
      (node (ref "C21") (pin "2") (pinfunction "2_2") (pintype "passive"))
      (node (ref "C22") (pin "2") (pinfunction "2_2") (pintype "passive"))
      (node (ref "C23") (pin "2") (pinfunction "2_2") (pintype "passive"))
      (node (ref "C24") (pin "1") (pinfunction "1_1") (pintype "passive"))
      (node (ref "C25") (pin "1") (pinfunction "1_1") (pintype "passive"))
      (node (ref "C26") (pin "1") (pinfunction "1_1") (pintype "passive"))
      (node (ref "C27") (pin "1") (pinfunction "1_1") (pintype "passive"))
      (node (ref "C28") (pin "1") (pinfunction "1_1") (pintype "passive"))
      (node (ref "C3") (pin "2") (pinfunction "2_2") (pintype "passive"))
      (node (ref "C30") (pin "1") (pinfunction "1_1") (pintype "passive"))
      (node (ref "C31") (pin "1") (pinfunction "1_1") (pintype "passive"))
      (node (ref "C32") (pin "1") (pinfunction "1_1") (pintype "passive"))
      (node (ref "C34") (pin "1") (pinfunction "1_1") (pintype "passive"))
      (node (ref "C35") (pin "1") (pinfunction "1_1") (pintype "passive"))
      (node (ref "C36") (pin "1") (pinfunction "1_1") (pintype "passive"))
      (node (ref "C37") (pin "1") (pinfunction "1_1") (pintype "passive"))
      (node (ref "C38") (pin "2") (pinfunction "2_2") (pintype "passive"))
      (node (ref "C39") (pin "2") (pinfunction "2_2") (pintype "passive"))
      (node (ref "C4") (pin "1") (pinfunction "1_1") (pintype "passive"))
      (node (ref "C40") (pin "2") (pinfunction "2_2") (pintype "passive"))
      (node (ref "C41") (pin "2") (pinfunction "2_2") (pintype "passive"))
      (node (ref "C42") (pin "1") (pinfunction "1_1") (pintype "passive"))
      (node (ref "C43") (pin "1") (pinfunction "1_1") (pintype "passive"))
      (node (ref "C44") (pin "1") (pinfunction "1_1") (pintype "passive"))
      (node (ref "C45") (pin "2") (pinfunction "2_2") (pintype "passive"))
      (node (ref "C46") (pin "2") (pinfunction "2_2") (pintype "passive"))
      (node (ref "C47") (pin "2") (pinfunction "2_2") (pintype "passive"))
      (node (ref "C48") (pin "2") (pinfunction "2_2") (pintype "passive"))
      (node (ref "C49") (pin "2") (pinfunction "2_2") (pintype "passive"))
      (node (ref "C5") (pin "1") (pinfunction "1_1") (pintype "passive"))
      (node (ref "C6") (pin "1") (pinfunction "1_1") (pintype "passive"))
      (node (ref "C7") (pin "1") (pinfunction "1_1") (pintype "passive"))
      (node (ref "C8") (pin "1") (pinfunction "1_1") (pintype "passive"))
      (node (ref "C9") (pin "1") (pinfunction "1_1") (pintype "passive"))
      (node (ref "D1") (pin "2") (pinfunction "K_2") (pintype "passive"))
      (node (ref "D2") (pin "2") (pinfunction "K_2") (pintype "passive"))
      (node (ref "D3") (pin "2") (pinfunction "K_2") (pintype "passive"))
      (node (ref "D4") (pin "2") (pinfunction "K_2") (pintype "passive"))
      (node (ref "D5") (pin "2") (pinfunction "K_2") (pintype "passive"))
      (node (ref "IC1") (pin "1") (pinfunction "GND_1_1") (pintype "passive"))
      (node (ref "IC1") (pin "40") (pinfunction "GND_2_40") (pintype "passive"))
      (node (ref "IC1") (pin "41") (pinfunction "GND_3_41") (pintype "passive"))
      (node (ref "IC1") (pin "42") (pinfunction "GND_4_42") (pintype "passive"))
      (node (ref "IC1") (pin "43") (pinfunction "GND_5_43") (pintype "passive"))
      (node (ref "IC1") (pin "44") (pinfunction "GND_6_44") (pintype "passive"))
      (node (ref "IC1") (pin "45") (pinfunction "GND_7_45") (pintype "passive"))
      (node (ref "IC1") (pin "46") (pinfunction "GND_8_46") (pintype "passive"))
      (node (ref "IC1") (pin "47") (pinfunction "GND_9_47") (pintype "passive"))
      (node (ref "IC1") (pin "48") (pinfunction "GND_10_48") (pintype "passive"))
      (node (ref "IC1") (pin "49") (pinfunction "GND_11_49") (pintype "passive"))
      (node (ref "IC2") (pin "5") (pinfunction "GND_TAB_5") (pintype "power_in"))
      (node (ref "P1") (pin "3") (pinfunction "3_3") (pintype "passive"))
      (node (ref "P2") (pin "1") (pinfunction "1_1") (pintype "passive"))
      (node (ref "P3") (pin "6") (pinfunction "6_6") (pintype "passive"))
      (node (ref "P4") (pin "6") (pinfunction "6_6") (pintype "passive"))
      (node (ref "R15") (pin "2") (pinfunction "2_2") (pintype "passive"))
      (node (ref "R23") (pin "2") (pinfunction "2_2") (pintype "passive"))
      (node (ref "R24") (pin "2") (pinfunction "2_2") (pintype "passive"))
      (node (ref "R25") (pin "1") (pinfunction "1_1") (pintype "passive"))
      (node (ref "R5") (pin "2") (pinfunction "2_2") (pintype "passive"))
      (node (ref "RST1") (pin "2") (pinfunction "2_2") (pintype "passive"))
      (node (ref "U1") (pin "12") (pinfunction "VSSA_12") (pintype "passive"))
      (node (ref "U1") (pin "18") (pinfunction "VSS_18") (pintype "passive"))
      (node (ref "U1") (pin "63") (pinfunction "VSS_63") (pintype "passive"))
      (node (ref "U2") (pin "2") (pinfunction "GND_2") (pintype "passive"))
      (node (ref "U4") (pin "49") (pinfunction "PAD_49") (pintype "passive"))
      (node (ref "U6") (pin "2") (pinfunction "GND_2") (pintype "passive"))
      (node (ref "U8") (pin "1") (pinfunction "VM_1") (pintype "passive"))
      (node (ref "U8") (pin "2") (pinfunction "VM_2") (pintype "passive"))
      (node (ref "U8") (pin "3") (pinfunction "VM_3") (pintype "passive"))
      (node (ref "U8") (pin "4") (pinfunction "VM_4") (pintype "passive"))
      (node (ref "USB1") (pin "A1") (pinfunction "GND_A1") (pintype "passive"))
      (node (ref "USB1") (pin "A12") (pinfunction "GND_A12") (pintype "passive"))
      (node (ref "USB1") (pin "B1") (pinfunction "GND_B1") (pintype "passive"))
      (node (ref "USB1") (pin "B12") (pinfunction "GND_B12") (pintype "passive"))
      (node (ref "X1") (pin "2") (pinfunction "2_2") (pintype "passive"))
      (node (ref "X1") (pin "4") (pinfunction "4_4") (pintype "passive"))
    )
    (net (code "78") (name "KEY_POS1") (class "Default")
      (node (ref "1") (pin "11") (pinfunction "11_11") (pintype "passive"))
      (node (ref "U1") (pin "8") (pinfunction "PC0_8") (pintype "passive"))
    )
    (net (code "79") (name "KEY_POS2") (class "Default")
      (node (ref "1") (pin "12") (pinfunction "12_12") (pintype "passive"))
      (node (ref "U1") (pin "9") (pinfunction "PC1_9") (pintype "passive"))
    )
    (net (code "80") (name "KEY_POS3") (class "Default")
      (node (ref "1") (pin "13") (pinfunction "13_13") (pintype "passive"))
      (node (ref "U1") (pin "10") (pinfunction "PC2_10") (pintype "passive"))
    )
    (net (code "81") (name "KEY_POS4") (class "Default")
      (node (ref "1") (pin "14") (pinfunction "14_14") (pintype "passive"))
      (node (ref "U1") (pin "11") (pinfunction "PC3_11") (pintype "passive"))
    )
    (net (code "82") (name "KEY_POS5") (class "Default")
      (node (ref "1") (pin "15") (pinfunction "15_15") (pintype "passive"))
      (node (ref "U1") (pin "24") (pinfunction "PC4_24") (pintype "passive"))
    )
    (net (code "83") (name "KEY_POS6") (class "Default")
      (node (ref "1") (pin "16") (pinfunction "16_16") (pintype "passive"))
      (node (ref "U1") (pin "25") (pinfunction "PC5_25") (pintype "passive"))
    )
    (net (code "84") (name "KEY_POS7") (class "Default")
      (node (ref "1") (pin "17") (pinfunction "17_17") (pintype "passive"))
      (node (ref "U1") (pin "37") (pinfunction "PC6_37") (pintype "passive"))
    )
    (net (code "85") (name "KEY_POS8") (class "Default")
      (node (ref "1") (pin "18") (pinfunction "18_18") (pintype "passive"))
      (node (ref "U1") (pin "38") (pinfunction "PC7_38") (pintype "passive"))
    )
    (net (code "86") (name "KEY_POS9") (class "Default")
      (node (ref "1") (pin "19") (pinfunction "19_19") (pintype "passive"))
      (node (ref "U1") (pin "39") (pinfunction "PC8_39") (pintype "passive"))
    )
    (net (code "87") (name "KEY_POS10") (class "Default")
      (node (ref "1") (pin "20") (pinfunction "20_20") (pintype "passive"))
      (node (ref "U1") (pin "53") (pinfunction "PC12_53") (pintype "passive"))
    )
    (net (code "88") (name "KEY_POS11") (class "Default")
      (node (ref "1") (pin "21") (pinfunction "21_21") (pintype "passive"))
      (node (ref "U1") (pin "54") (pinfunction "PD2_54") (pintype "passive"))
    )
    (net (code "89") (name "KEY_POS12") (class "Default")
      (node (ref "1") (pin "22") (pinfunction "22_22") (pintype "passive"))
      (node (ref "U1") (pin "2") (pinfunction "PC13_2") (pintype "passive"))
    )
    (net (code "90") (name "KEY_POS13") (class "Default")
      (node (ref "1") (pin "23") (pinfunction "23_23") (pintype "passive"))
      (node (ref "U1") (pin "3") (pinfunction "OSC32_IN/PC14_3") (pintype "passive"))
    )
    (net (code "91") (name "KEY_POS14") (class "Default")
      (node (ref "1") (pin "24") (pinfunction "24_24") (pintype "passive"))
      (node (ref "U1") (pin "4") (pinfunction "OSC32_OUT/PC15_4") (pintype "passive"))
    )
    (net (code "92") (name "KEY_SEG1") (class "Default")
      (node (ref "1") (pin "31") (pinfunction "31_31") (pintype "passive"))
      (node (ref "U1") (pin "27") (pinfunction "PB1_27") (pintype "passive"))
    )
    (net (code "93") (name "KEY_SEG2") (class "Default")
      (node (ref "1") (pin "30") (pinfunction "30_30") (pintype "passive"))
      (node (ref "U1") (pin "29") (pinfunction "PB10_29") (pintype "passive"))
    )
    (net (code "94") (name "KEY_SEG3") (class "Default")
      (node (ref "1") (pin "29") (pinfunction "29_29") (pintype "passive"))
      (node (ref "U1") (pin "30") (pinfunction "PB11_30") (pintype "passive"))
    )
    (net (code "95") (name "KEY_SEG4") (class "Default")
      (node (ref "1") (pin "28") (pinfunction "28_28") (pintype "passive"))
      (node (ref "U1") (pin "33") (pinfunction "PB12_33") (pintype "passive"))
    )
    (net (code "96") (name "KEY_SEG5") (class "Default")
      (node (ref "1") (pin "27") (pinfunction "27_27") (pintype "passive"))
      (node (ref "U1") (pin "34") (pinfunction "PB13_34") (pintype "passive"))
    )
    (net (code "97") (name "KEY_SEG6") (class "Default")
      (node (ref "1") (pin "26") (pinfunction "26_26") (pintype "passive"))
      (node (ref "U1") (pin "35") (pinfunction "PB14_35") (pintype "passive"))
    )
    (net (code "98") (name "Net-(1-Pad35)") (class "Default")
      (node (ref "1") (pin "35") (pinfunction "35_35") (pintype "passive"))
      (node (ref "R1") (pin "5") (pinfunction "5_5") (pintype "passive"))
    )
    (net (code "99") (name "Net-(1-Pad36)") (class "Default")
      (node (ref "1") (pin "36") (pinfunction "36_36") (pintype "passive"))
      (node (ref "R1") (pin "6") (pinfunction "6_6") (pintype "passive"))
    )
    (net (code "100") (name "Net-(1-Pad37)") (class "Default")
      (node (ref "1") (pin "37") (pinfunction "37_37") (pintype "passive"))
      (node (ref "R1") (pin "7") (pinfunction "7_7") (pintype "passive"))
    )
    (net (code "101") (name "Net-(1-Pad38)") (class "Default")
      (node (ref "1") (pin "38") (pinfunction "38_38") (pintype "passive"))
      (node (ref "R1") (pin "8") (pinfunction "8_8") (pintype "passive"))
    )
    (net (code "102") (name "Net-(D1-A)") (class "Default")
      (node (ref "1") (pin "9") (pinfunction "9_9") (pintype "passive"))
      (node (ref "C8") (pin "2") (pinfunction "2_2") (pintype "passive"))
      (node (ref "D1") (pin "1") (pinfunction "A_1") (pintype "passive"))
      (node (ref "R9") (pin "8") (pinfunction "8_8") (pintype "passive"))
    )
    (net (code "103") (name "Net-(D2-A)") (class "Default")
      (node (ref "1") (pin "8") (pinfunction "8_8") (pintype "passive"))
      (node (ref "C9") (pin "2") (pinfunction "2_2") (pintype "passive"))
      (node (ref "D2") (pin "1") (pinfunction "A_1") (pintype "passive"))
      (node (ref "R9") (pin "7") (pinfunction "7_7") (pintype "passive"))
    )
    (net (code "104") (name "Net-(D3-A)") (class "Default")
      (node (ref "1") (pin "7") (pinfunction "7_7") (pintype "passive"))
      (node (ref "C10") (pin "2") (pinfunction "2_2") (pintype "passive"))
      (node (ref "D3") (pin "1") (pinfunction "A_1") (pintype "passive"))
      (node (ref "R9") (pin "6") (pinfunction "6_6") (pintype "passive"))
    )
    (net (code "105") (name "Net-(D6-K)") (class "Default")
      (node (ref "D6") (pin "1") (pinfunction "K_1") (pintype "passive"))
      (node (ref "D7") (pin "1") (pinfunction "K_1") (pintype "passive"))
      (node (ref "R26") (pin "1") (pinfunction "1_1") (pintype "passive"))
    )
    (net (code "106") (name "Net-(F1-Pad2)") (class "Default")
      (node (ref "F1") (pin "2") (pinfunction "2_2") (pintype "passive"))
      (node (ref "P1") (pin "4") (pinfunction "4_4") (pintype "passive"))
    )
    (net (code "107") (name "Net-(IC2-SENSE)") (class "Default")
      (node (ref "IC2") (pin "4") (pinfunction "SENSE_4") (pintype "passive"))
      (node (ref "R28") (pin "1") (pinfunction "1_1") (pintype "passive"))
    )
    (net (code "108") (name "Net-(IC2-~{SD})") (class "Default")
      (node (ref "IC2") (pin "1") (pinfunction "~{SD}_1") (pintype "passive"))
      (node (ref "R25") (pin "2") (pinfunction "2_2") (pintype "passive"))
      (node (ref "R27") (pin "2") (pinfunction "2_2") (pintype "passive"))
    )
    (net (code "109") (name "Net-(P1-Pad1)") (class "Default")
      (node (ref "P1") (pin "1") (pinfunction "1_1") (pintype "passive"))
      (node (ref "R2") (pin "2") (pinfunction "2_2") (pintype "passive"))
    )
    (net (code "110") (name "Net-(P1-Pad2)") (class "Default")
      (node (ref "P1") (pin "2") (pinfunction "2_2") (pintype "passive"))
      (node (ref "R3") (pin "2") (pinfunction "2_2") (pintype "passive"))
    )
    (net (code "111") (name "Net-(P3-Pad2)") (class "Default")
      (node (ref "P3") (pin "2") (pinfunction "2_2") (pintype "passive"))
      (node (ref "R20") (pin "1") (pinfunction "1_1") (pintype "passive"))
    )
    (net (code "112") (name "Net-(P3-Pad3)") (class "Default")
      (node (ref "P3") (pin "3") (pinfunction "3_3") (pintype "passive"))
      (node (ref "R20") (pin "2") (pinfunction "2_2") (pintype "passive"))
    )
    (net (code "113") (name "Net-(P3-Pad4)") (class "Default")
      (node (ref "P3") (pin "4") (pinfunction "4_4") (pintype "passive"))
      (node (ref "R20") (pin "3") (pinfunction "3_3") (pintype "passive"))
    )
    (net (code "114") (name "Net-(P3-Pad5)") (class "Default")
      (node (ref "P3") (pin "5") (pinfunction "5_5") (pintype "passive"))
      (node (ref "R20") (pin "4") (pinfunction "4_4") (pintype "passive"))
    )
    (net (code "115") (name "Net-(Q1-B)") (class "Default")
      (node (ref "Q1") (pin "1") (pinfunction "B_1") (pintype "passive"))
      (node (ref "R4") (pin "2") (pinfunction "2_2") (pintype "passive"))
      (node (ref "R6") (pin "1") (pinfunction "1_1") (pintype "passive"))
    )
    (net (code "116") (name "Net-(Q1-C)") (class "Default")
      (node (ref "Q1") (pin "3") (pinfunction "C_3") (pintype "passive"))
      (node (ref "R7") (pin "2") (pinfunction "2_2") (pintype "passive"))
    )
    (net (code "117") (name "Net-(R14-Pad2)") (class "Default")
      (node (ref "R14") (pin "2") (pinfunction "2_2") (pintype "passive"))
      (node (ref "R15") (pin "1") (pinfunction "1_1") (pintype "passive"))
      (node (ref "U6") (pin "3") (pinfunction "EN_3") (pintype "passive"))
    )
    (net (code "118") (name "Net-(U1-RCC_OSC_IN{slash}PH0)") (class "Default")
      (node (ref "C1") (pin "1") (pinfunction "1_1") (pintype "passive"))
      (node (ref "U1") (pin "5") (pinfunction "RCC_OSC_IN/PH0_5") (pintype "passive"))
      (node (ref "X1") (pin "3") (pinfunction "3_3") (pintype "passive"))
    )
    (net (code "119") (name "Net-(U1-RCC_OSC_OUT{slash}PH1)") (class "Default")
      (node (ref "C2") (pin "1") (pinfunction "1_1") (pintype "passive"))
      (node (ref "U1") (pin "6") (pinfunction "RCC_OSC_OUT/PH1_6") (pintype "passive"))
      (node (ref "X1") (pin "1") (pinfunction "1_1") (pintype "passive"))
    )
    (net (code "120") (name "Net-(U1-VCAP_1)") (class "Default")
      (node (ref "C13") (pin "2") (pinfunction "2_2") (pintype "passive"))
      (node (ref "U1") (pin "31") (pinfunction "VCAP_1_31") (pintype "passive"))
    )
    (net (code "121") (name "Net-(U1-VCAP_2)") (class "Default")
      (node (ref "C14") (pin "2") (pinfunction "2_2") (pintype "passive"))
      (node (ref "U1") (pin "47") (pinfunction "VCAP_2_47") (pintype "passive"))
    )
    (net (code "122") (name "Net-(U8-VDD)") (class "Default")
      (node (ref "C50") (pin "2") (pinfunction "2_2") (pintype "passive"))
      (node (ref "R33") (pin "2") (pinfunction "2_2") (pintype "passive"))
      (node (ref "U8") (pin "6") (pinfunction "VDD_6") (pintype "passive"))
    )
    (net (code "123") (name "USBVCC") (class "Default")
      (node (ref "C24") (pin "2") (pinfunction "2_2") (pintype "passive"))
      (node (ref "U3") (pin "1") (pinfunction "S1_1") (pintype "passive"))
      (node (ref "U3") (pin "3") (pinfunction "S2_3") (pintype "passive"))
      (node (ref "U4") (pin "12") (pinfunction "VBUS_C_12") (pintype "passive"))
      (node (ref "USB1") (pin "A4") (pinfunction "VBUS_A4") (pintype "passive"))
      (node (ref "USB1") (pin "A9") (pinfunction "VBUS_A9") (pintype "passive"))
      (node (ref "USB1") (pin "B4") (pinfunction "VBUS_B4") (pintype "passive"))
      (node (ref "USB1") (pin "B9") (pinfunction "VBUS_B9") (pintype "passive"))
    )
    (net (code "124") (name "VCC") (class "Default")
      (node (ref "D6") (pin "2") (pinfunction "A_2") (pintype "passive"))
      (node (ref "R21") (pin "2") (pinfunction "2_2") (pintype "passive"))
      (node (ref "R22") (pin "2") (pinfunction "2_2") (pintype "passive"))
      (node (ref "U4") (pin "19") (pinfunction "VCC_19") (pintype "passive"))
    )
    (net (code "125") (name "VCC3V3") (class "Default")
      (node (ref "C11") (pin "2") (pinfunction "2_2") (pintype "passive"))
      (node (ref "C12") (pin "2") (pinfunction "2_2") (pintype "passive"))
      (node (ref "C20") (pin "1") (pinfunction "1_1") (pintype "passive"))
      (node (ref "C21") (pin "1") (pinfunction "1_1") (pintype "passive"))
      (node (ref "C4") (pin "2") (pinfunction "2_2") (pintype "passive"))
      (node (ref "C43") (pin "2") (pinfunction "2_2") (pintype "passive"))
      (node (ref "C44") (pin "2") (pinfunction "2_2") (pintype "passive"))
      (node (ref "C5") (pin "2") (pinfunction "2_2") (pintype "passive"))
      (node (ref "C6") (pin "2") (pinfunction "2_2") (pintype "passive"))
      (node (ref "C7") (pin "2") (pinfunction "2_2") (pintype "passive"))
      (node (ref "F1") (pin "1") (pinfunction "1_1") (pintype "passive"))
      (node (ref "IC1") (pin "2") (pinfunction "3V3_2") (pintype "passive"))
      (node (ref "P3") (pin "1") (pinfunction "1_1") (pintype "passive"))
      (node (ref "R12") (pin "1") (pinfunction "1_1") (pintype "passive"))
      (node (ref "R16") (pin "1") (pinfunction "1_1") (pintype "passive"))
      (node (ref "R17") (pin "1") (pinfunction "1_1") (pintype "passive"))
      (node (ref "R18") (pin "1") (pinfunction "1_1") (pintype "passive"))
      (node (ref "R19") (pin "2") (pinfunction "2_2") (pintype "passive"))
      (node (ref "R8") (pin "2") (pinfunction "2_2") (pintype "passive"))
      (node (ref "U1") (pin "1") (pinfunction "VBAT_1") (pintype "passive"))
      (node (ref "U1") (pin "19") (pinfunction "VDD_19") (pintype "passive"))
      (node (ref "U1") (pin "32") (pinfunction "VDD_32") (pintype "passive"))
      (node (ref "U1") (pin "48") (pinfunction "VDD_48") (pintype "passive"))
      (node (ref "U1") (pin "64") (pinfunction "VDD_64") (pintype "passive"))
      (node (ref "U2") (pin "5") (pinfunction "VOUT_5") (pintype "passive"))
    )
    (net (code "126") (name "VCC3V3_1A") (class "Default")
      (node (ref "1") (pin "33") (pinfunction "33_33") (pintype "passive"))
      (node (ref "C48") (pin "1") (pinfunction "1_1") (pintype "passive"))
      (node (ref "C49") (pin "1") (pinfunction "1_1") (pintype "passive"))
      (node (ref "IC2") (pin "3") (pinfunction "OUT_3") (pintype "output"))
      (node (ref "R28") (pin "2") (pinfunction "2_2") (pintype "passive"))
    )
    (net (code "127") (name "VCC_BUS") (class "Default")
      (node (ref "C18") (pin "1") (pinfunction "1_1") (pintype "passive"))
      (node (ref "C19") (pin "1") (pinfunction "1_1") (pintype "passive"))
      (node (ref "C38") (pin "1") (pinfunction "1_1") (pintype "passive"))
      (node (ref "C39") (pin "1") (pinfunction "1_1") (pintype "passive"))
      (node (ref "C46") (pin "1") (pinfunction "1_1") (pintype "passive"))
      (node (ref "C47") (pin "1") (pinfunction "1_1") (pintype "passive"))
      (node (ref "IC2") (pin "2") (pinfunction "IN_2") (pintype "input"))
      (node (ref "R26") (pin "2") (pinfunction "2_2") (pintype "passive"))
      (node (ref "U2") (pin "1") (pinfunction "EN_1") (pintype "passive"))
      (node (ref "U2") (pin "3") (pinfunction "EN_3") (pintype "passive"))
      (node (ref "U6") (pin "1") (pinfunction "EN_1") (pintype "passive"))
    )
    (net (code "128") (name "VCC_LCD") (class "Default")
      (node (ref "1") (pin "39") (pinfunction "39_39") (pintype "passive"))
      (node (ref "C40") (pin "1") (pinfunction "1_1") (pintype "passive"))
      (node (ref "C41") (pin "1") (pinfunction "1_1") (pintype "passive"))
      (node (ref "P2") (pin "4") (pinfunction "4_4") (pintype "passive"))
      (node (ref "P2") (pin "6") (pinfunction "6_6") (pintype "passive"))
      (node (ref "Q1") (pin "2") (pinfunction "E_2") (pintype "passive"))
      (node (ref "R6") (pin "2") (pinfunction "2_2") (pintype "passive"))
      (node (ref "U6") (pin "5") (pinfunction "VOUT_5") (pintype "passive"))
    )
    (net (code "129") (name "unconnected-(IC1-IO1-Pad39)") (class "Default")
      (node (ref "IC1") (pin "39") (pinfunction "IO1_39") (pintype "passive+no_connect"))
    )
    (net (code "130") (name "unconnected-(IC1-IO2-Pad38)") (class "Default")
      (node (ref "IC1") (pin "38") (pinfunction "IO2_38") (pintype "passive+no_connect"))
    )
    (net (code "131") (name "unconnected-(IC1-IO3-Pad15)") (class "Default")
      (node (ref "IC1") (pin "15") (pinfunction "IO3_15") (pintype "passive+no_connect"))
    )
    (net (code "132") (name "unconnected-(IC1-IO4-Pad4)") (class "Default")
      (node (ref "IC1") (pin "4") (pinfunction "IO4_4") (pintype "passive+no_connect"))
    )
    (net (code "133") (name "unconnected-(IC1-IO5-Pad5)") (class "Default")
      (node (ref "IC1") (pin "5") (pinfunction "IO5_5") (pintype "passive+no_connect"))
    )
    (net (code "134") (name "unconnected-(IC1-IO6-Pad6)") (class "Default")
      (node (ref "IC1") (pin "6") (pinfunction "IO6_6") (pintype "passive+no_connect"))
    )
    (net (code "135") (name "unconnected-(IC1-IO7-Pad7)") (class "Default")
      (node (ref "IC1") (pin "7") (pinfunction "IO7_7") (pintype "passive+no_connect"))
    )
    (net (code "136") (name "unconnected-(IC1-IO8-Pad12)") (class "Default")
      (node (ref "IC1") (pin "12") (pinfunction "IO8_12") (pintype "passive+no_connect"))
    )
    (net (code "137") (name "unconnected-(IC1-IO9-Pad17)") (class "Default")
      (node (ref "IC1") (pin "17") (pinfunction "IO9_17") (pintype "passive+no_connect"))
    )
    (net (code "138") (name "unconnected-(IC1-IO10-Pad18)") (class "Default")
      (node (ref "IC1") (pin "18") (pinfunction "IO10_18") (pintype "passive+no_connect"))
    )
    (net (code "139") (name "unconnected-(IC1-IO11-Pad19)") (class "Default")
      (node (ref "IC1") (pin "19") (pinfunction "IO11_19") (pintype "passive+no_connect"))
    )
    (net (code "140") (name "unconnected-(IC1-IO12-Pad20)") (class "Default")
      (node (ref "IC1") (pin "20") (pinfunction "IO12_20") (pintype "passive+no_connect"))
    )
    (net (code "141") (name "unconnected-(IC1-IO13-Pad21)") (class "Default")
      (node (ref "IC1") (pin "21") (pinfunction "IO13_21") (pintype "passive+no_connect"))
    )
    (net (code "142") (name "unconnected-(IC1-IO14-Pad22)") (class "Default")
      (node (ref "IC1") (pin "22") (pinfunction "IO14_22") (pintype "passive+no_connect"))
    )
    (net (code "143") (name "unconnected-(IC1-IO15-Pad8)") (class "Default")
      (node (ref "IC1") (pin "8") (pinfunction "IO15_8") (pintype "passive+no_connect"))
    )
    (net (code "144") (name "unconnected-(IC1-IO16-Pad9)") (class "Default")
      (node (ref "IC1") (pin "9") (pinfunction "IO16_9") (pintype "passive+no_connect"))
    )
    (net (code "145") (name "unconnected-(IC1-IO19-Pad13)") (class "Default")
      (node (ref "IC1") (pin "13") (pinfunction "IO19_13") (pintype "passive+no_connect"))
    )
    (net (code "146") (name "unconnected-(IC1-IO20-Pad14)") (class "Default")
      (node (ref "IC1") (pin "14") (pinfunction "IO20_14") (pintype "passive+no_connect"))
    )
    (net (code "147") (name "unconnected-(IC1-IO21-Pad23)") (class "Default")
      (node (ref "IC1") (pin "23") (pinfunction "IO21_23") (pintype "passive+no_connect"))
    )
    (net (code "148") (name "unconnected-(IC1-IO35-Pad28)") (class "Default")
      (node (ref "IC1") (pin "28") (pinfunction "IO35_28") (pintype "passive+no_connect"))
    )
    (net (code "149") (name "unconnected-(IC1-IO36-Pad29)") (class "Default")
      (node (ref "IC1") (pin "29") (pinfunction "IO36_29") (pintype "passive+no_connect"))
    )
    (net (code "150") (name "unconnected-(IC1-IO37-Pad30)") (class "Default")
      (node (ref "IC1") (pin "30") (pinfunction "IO37_30") (pintype "passive+no_connect"))
    )
    (net (code "151") (name "unconnected-(IC1-IO38-Pad31)") (class "Default")
      (node (ref "IC1") (pin "31") (pinfunction "IO38_31") (pintype "passive+no_connect"))
    )
    (net (code "152") (name "unconnected-(IC1-IO39-Pad32)") (class "Default")
      (node (ref "IC1") (pin "32") (pinfunction "IO39_32") (pintype "passive+no_connect"))
    )
    (net (code "153") (name "unconnected-(IC1-IO40-Pad33)") (class "Default")
      (node (ref "IC1") (pin "33") (pinfunction "IO40_33") (pintype "passive+no_connect"))
    )
    (net (code "154") (name "unconnected-(IC1-IO41-Pad34)") (class "Default")
      (node (ref "IC1") (pin "34") (pinfunction "IO41_34") (pintype "passive+no_connect"))
    )
    (net (code "155") (name "unconnected-(IC1-IO42-Pad35)") (class "Default")
      (node (ref "IC1") (pin "35") (pinfunction "IO42_35") (pintype "passive+no_connect"))
    )
    (net (code "156") (name "unconnected-(IC1-IO45-Pad26)") (class "Default")
      (node (ref "IC1") (pin "26") (pinfunction "IO45_26") (pintype "passive+no_connect"))
    )
    (net (code "157") (name "unconnected-(IC1-IO46-Pad16)") (class "Default")
      (node (ref "IC1") (pin "16") (pinfunction "IO46_16") (pintype "passive+no_connect"))
    )
    (net (code "158") (name "unconnected-(IC1-IO47-Pad24)") (class "Default")
      (node (ref "IC1") (pin "24") (pinfunction "IO47_24") (pintype "passive+no_connect"))
    )
    (net (code "159") (name "unconnected-(IC1-IO48-Pad25)") (class "Default")
      (node (ref "IC1") (pin "25") (pinfunction "IO48_25") (pintype "passive+no_connect"))
    )
    (net (code "160") (name "unconnected-(P1-PadMP1)") (class "Default")
      (node (ref "P1") (pin "MP1") (pinfunction "MP1_MP1") (pintype "passive+no_connect"))
    )
    (net (code "161") (name "unconnected-(P1-PadMP2)") (class "Default")
      (node (ref "P1") (pin "MP2") (pinfunction "MP2_MP2") (pintype "passive+no_connect"))
    )
    (net (code "162") (name "unconnected-(P2-PadMP1)") (class "Default")
      (node (ref "P2") (pin "MP1") (pinfunction "MP1_MP1") (pintype "passive+no_connect"))
    )
    (net (code "163") (name "unconnected-(P2-PadMP2)") (class "Default")
      (node (ref "P2") (pin "MP2") (pinfunction "MP2_MP2") (pintype "passive+no_connect"))
    )
    (net (code "164") (name "unconnected-(P3-PadMP1)") (class "Default")
      (node (ref "P3") (pin "MP1") (pinfunction "MP1_MP1") (pintype "passive+no_connect"))
    )
    (net (code "165") (name "unconnected-(P3-PadMP2)") (class "Default")
      (node (ref "P3") (pin "MP2") (pinfunction "MP2_MP2") (pintype "passive+no_connect"))
    )
    (net (code "166") (name "unconnected-(P4-PadMP1)") (class "Default")
      (node (ref "P4") (pin "MP1") (pinfunction "MP1_MP1") (pintype "passive+no_connect"))
    )
    (net (code "167") (name "unconnected-(P4-PadMP2)") (class "Default")
      (node (ref "P4") (pin "MP2") (pinfunction "MP2_MP2") (pintype "passive+no_connect"))
    )
    (net (code "168") (name "unconnected-(R9-Pad4)") (class "Default")
      (node (ref "R9") (pin "4") (pinfunction "4_4") (pintype "passive"))
    )
    (net (code "169") (name "unconnected-(R9-Pad5)") (class "Default")
      (node (ref "R9") (pin "5") (pinfunction "5_5") (pintype "passive"))
    )
    (net (code "170") (name "unconnected-(R34-Pad2)") (class "Default")
      (node (ref "R34") (pin "2") (pinfunction "2_2") (pintype "passive+no_connect"))
    )
    (net (code "171") (name "unconnected-(R35-Pad2)") (class "Default")
      (node (ref "R35") (pin "2") (pinfunction "2_2") (pintype "passive+no_connect"))
    )
    (net (code "172") (name "unconnected-(U2-NC-Pad4)") (class "Default")
      (node (ref "U2") (pin "4") (pinfunction "NC_4") (pintype "passive+no_connect"))
    )
    (net (code "173") (name "unconnected-(U6-NC-Pad4)") (class "Default")
      (node (ref "U6") (pin "4") (pinfunction "NC_4") (pintype "passive+no_connect"))
    )
    (net (code "174") (name "unconnected-(USB1-RX1+-PadB11)") (class "Default")
      (node (ref "USB1") (pin "B11") (pinfunction "RX1+_B11") (pintype "passive+no_connect"))
    )
    (net (code "175") (name "unconnected-(USB1-RX1--PadB10)") (class "Default")
      (node (ref "USB1") (pin "B10") (pinfunction "RX1-_B10") (pintype "passive+no_connect"))
    )
    (net (code "176") (name "unconnected-(USB1-RX2+-PadA11)") (class "Default")
      (node (ref "USB1") (pin "A11") (pinfunction "RX2+_A11") (pintype "passive+no_connect"))
    )
    (net (code "177") (name "unconnected-(USB1-RX2--PadA10)") (class "Default")
      (node (ref "USB1") (pin "A10") (pinfunction "RX2-_A10") (pintype "passive+no_connect"))
    )
    (net (code "178") (name "unconnected-(USB1-SBU1-PadA8)") (class "Default")
      (node (ref "USB1") (pin "A8") (pinfunction "SBU1_A8") (pintype "passive+no_connect"))
    )
    (net (code "179") (name "unconnected-(USB1-SBU2-PadB8)") (class "Default")
      (node (ref "USB1") (pin "B8") (pinfunction "SBU2_B8") (pintype "passive+no_connect"))
    )
    (net (code "180") (name "unconnected-(USB1-SH1-Pad1)") (class "Default")
      (node (ref "USB1") (pin "1") (pinfunction "SH1_1") (pintype "passive+no_connect"))
    )
    (net (code "181") (name "unconnected-(USB1-SH2-Pad2)") (class "Default")
      (node (ref "USB1") (pin "2") (pinfunction "SH2_2") (pintype "passive+no_connect"))
    )
    (net (code "182") (name "unconnected-(USB1-SH3-Pad3)") (class "Default")
      (node (ref "USB1") (pin "3") (pinfunction "SH3_3") (pintype "passive+no_connect"))
    )
    (net (code "183") (name "unconnected-(USB1-SH4-Pad4)") (class "Default")
      (node (ref "USB1") (pin "4") (pinfunction "SH4_4") (pintype "passive+no_connect"))
    )
    (net (code "184") (name "unconnected-(USB1-TX1+-PadA2)") (class "Default")
      (node (ref "USB1") (pin "A2") (pinfunction "TX1+_A2") (pintype "passive+no_connect"))
    )
    (net (code "185") (name "unconnected-(USB1-TX1--PadA3)") (class "Default")
      (node (ref "USB1") (pin "A3") (pinfunction "TX1-_A3") (pintype "passive+no_connect"))
    )
    (net (code "186") (name "unconnected-(USB1-TX2+-PadB2)") (class "Default")
      (node (ref "USB1") (pin "B2") (pinfunction "TX2+_B2") (pintype "passive+no_connect"))
    )
    (net (code "187") (name "unconnected-(USB1-TX2--PadB3)") (class "Default")
      (node (ref "USB1") (pin "B3") (pinfunction "TX2-_B3") (pintype "passive+no_connect"))
    )
  )
)
